# LautIO.net
KiCad netlist of a schematic drawn in EAGLE
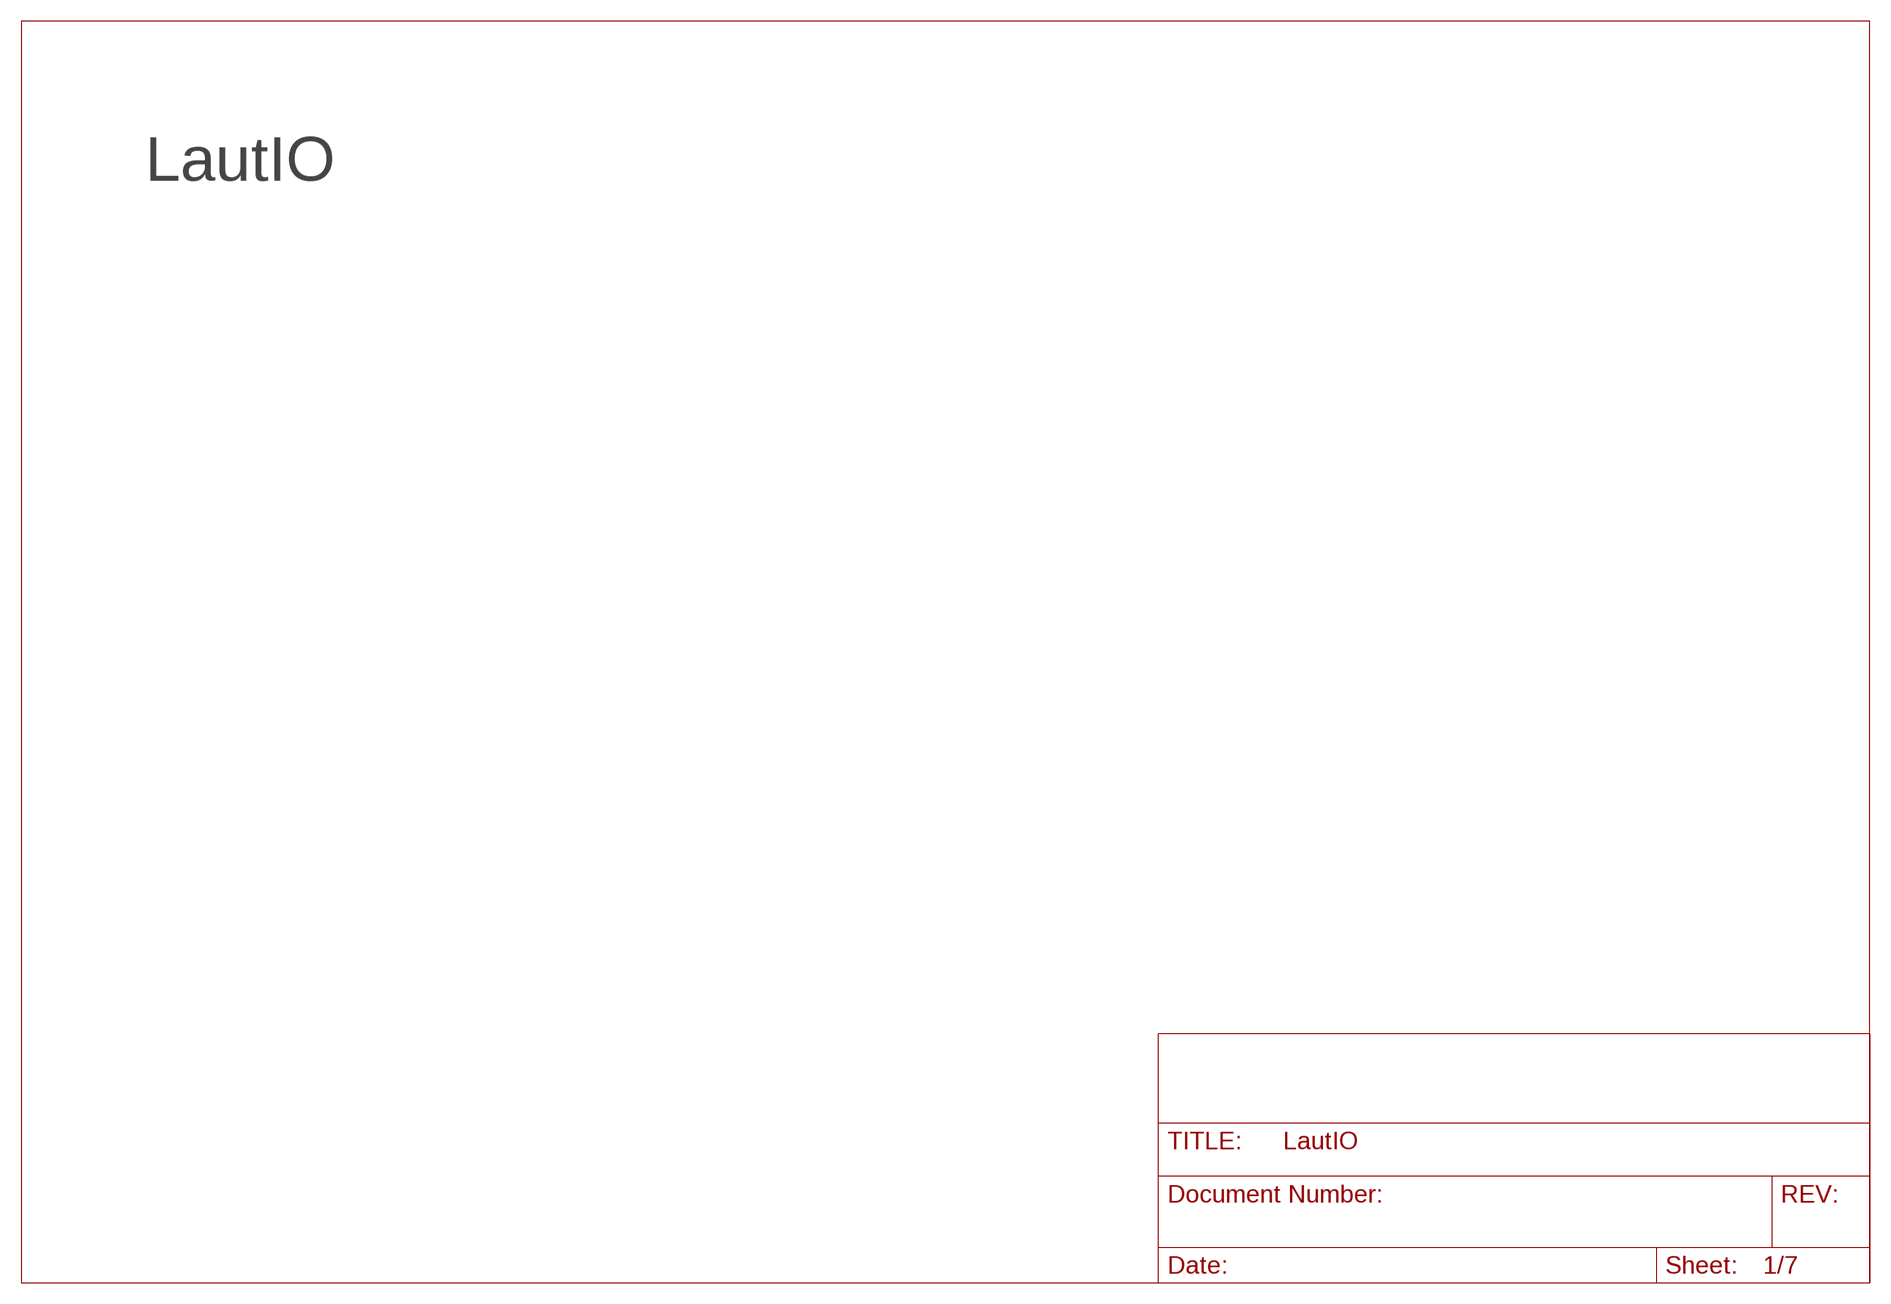
[diagram p0: schematic, sheet 1]
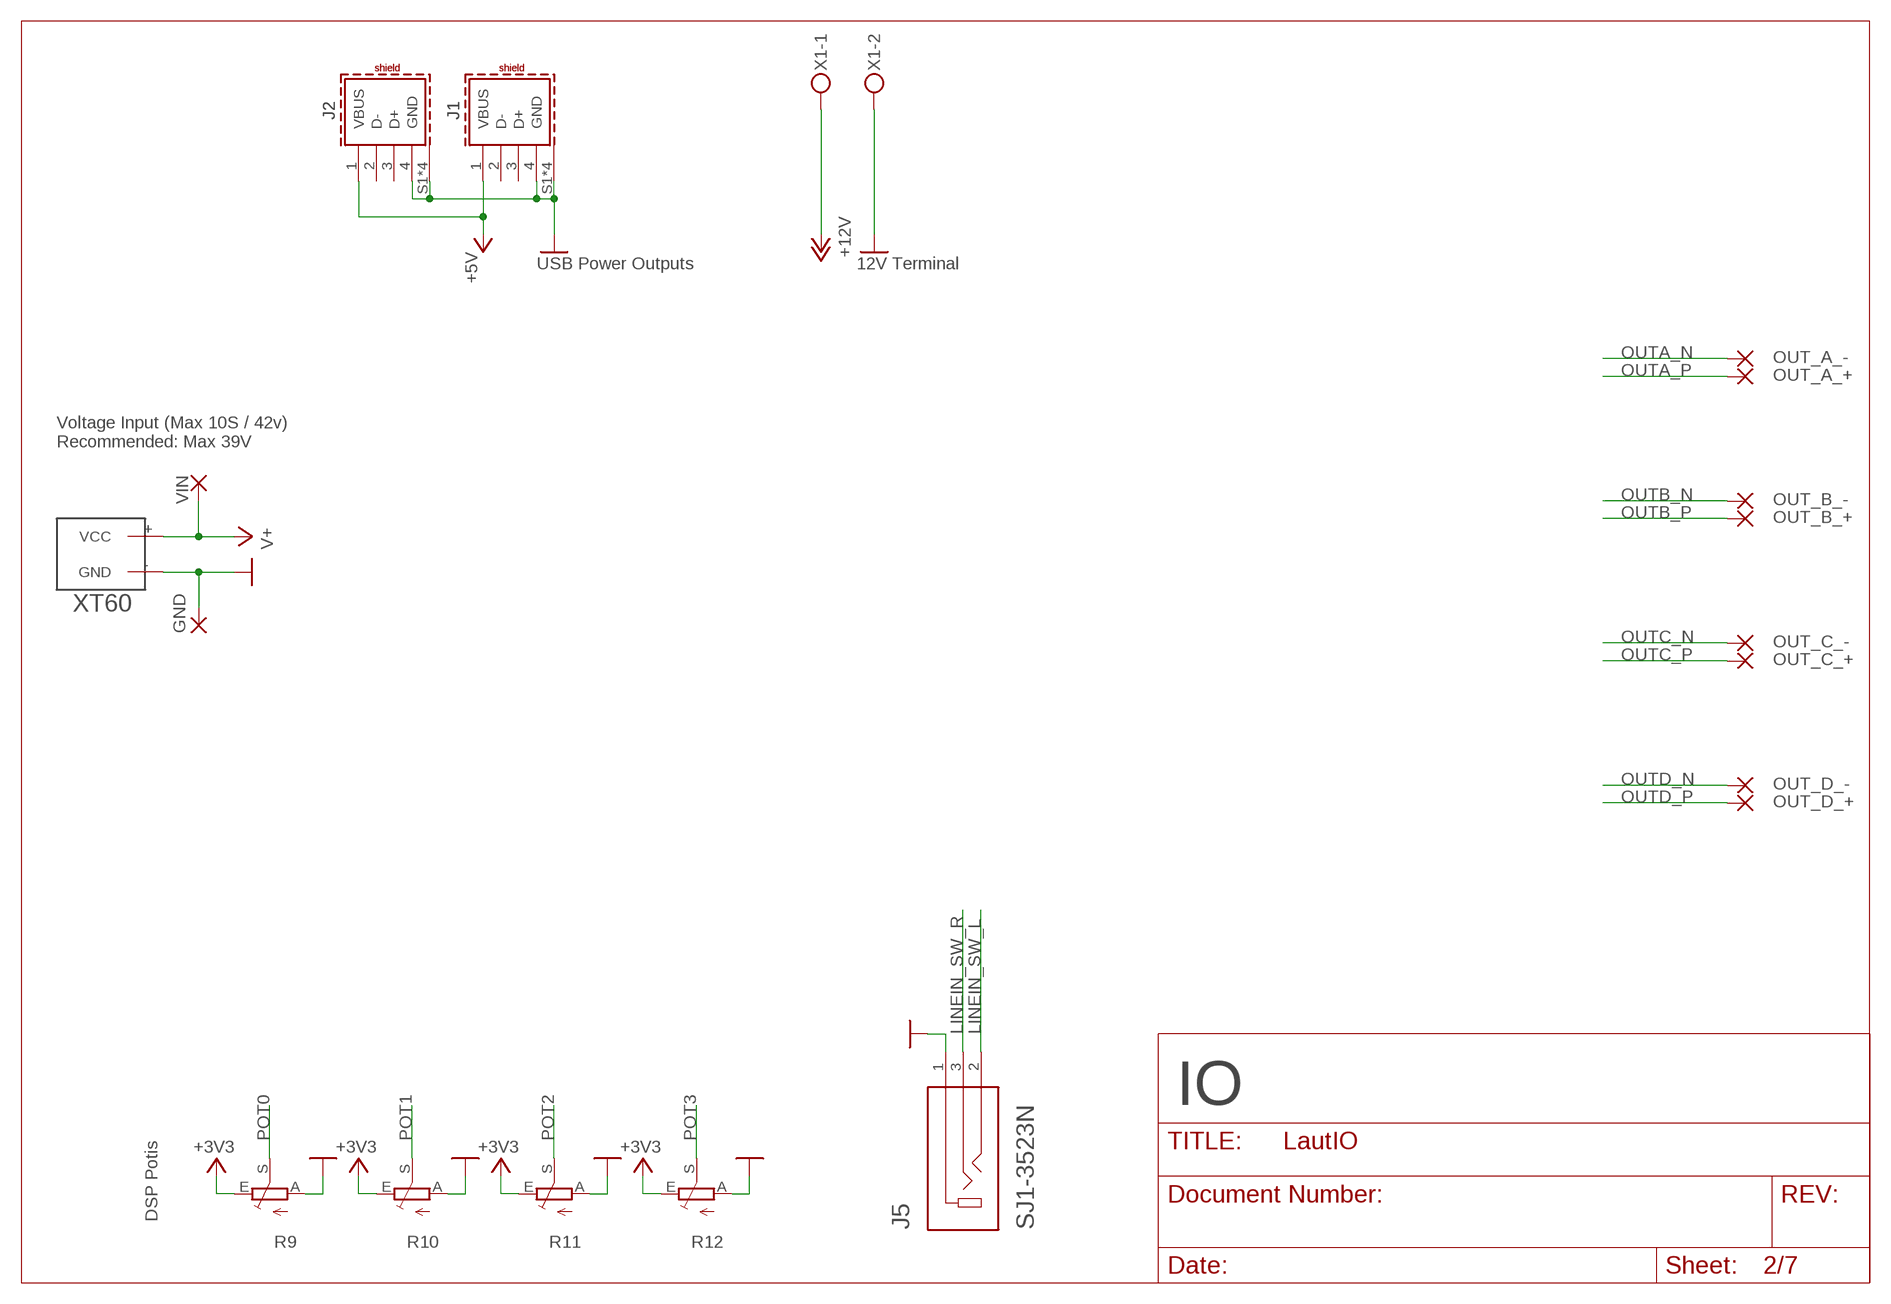
[diagram p1: schematic, sheet 2]
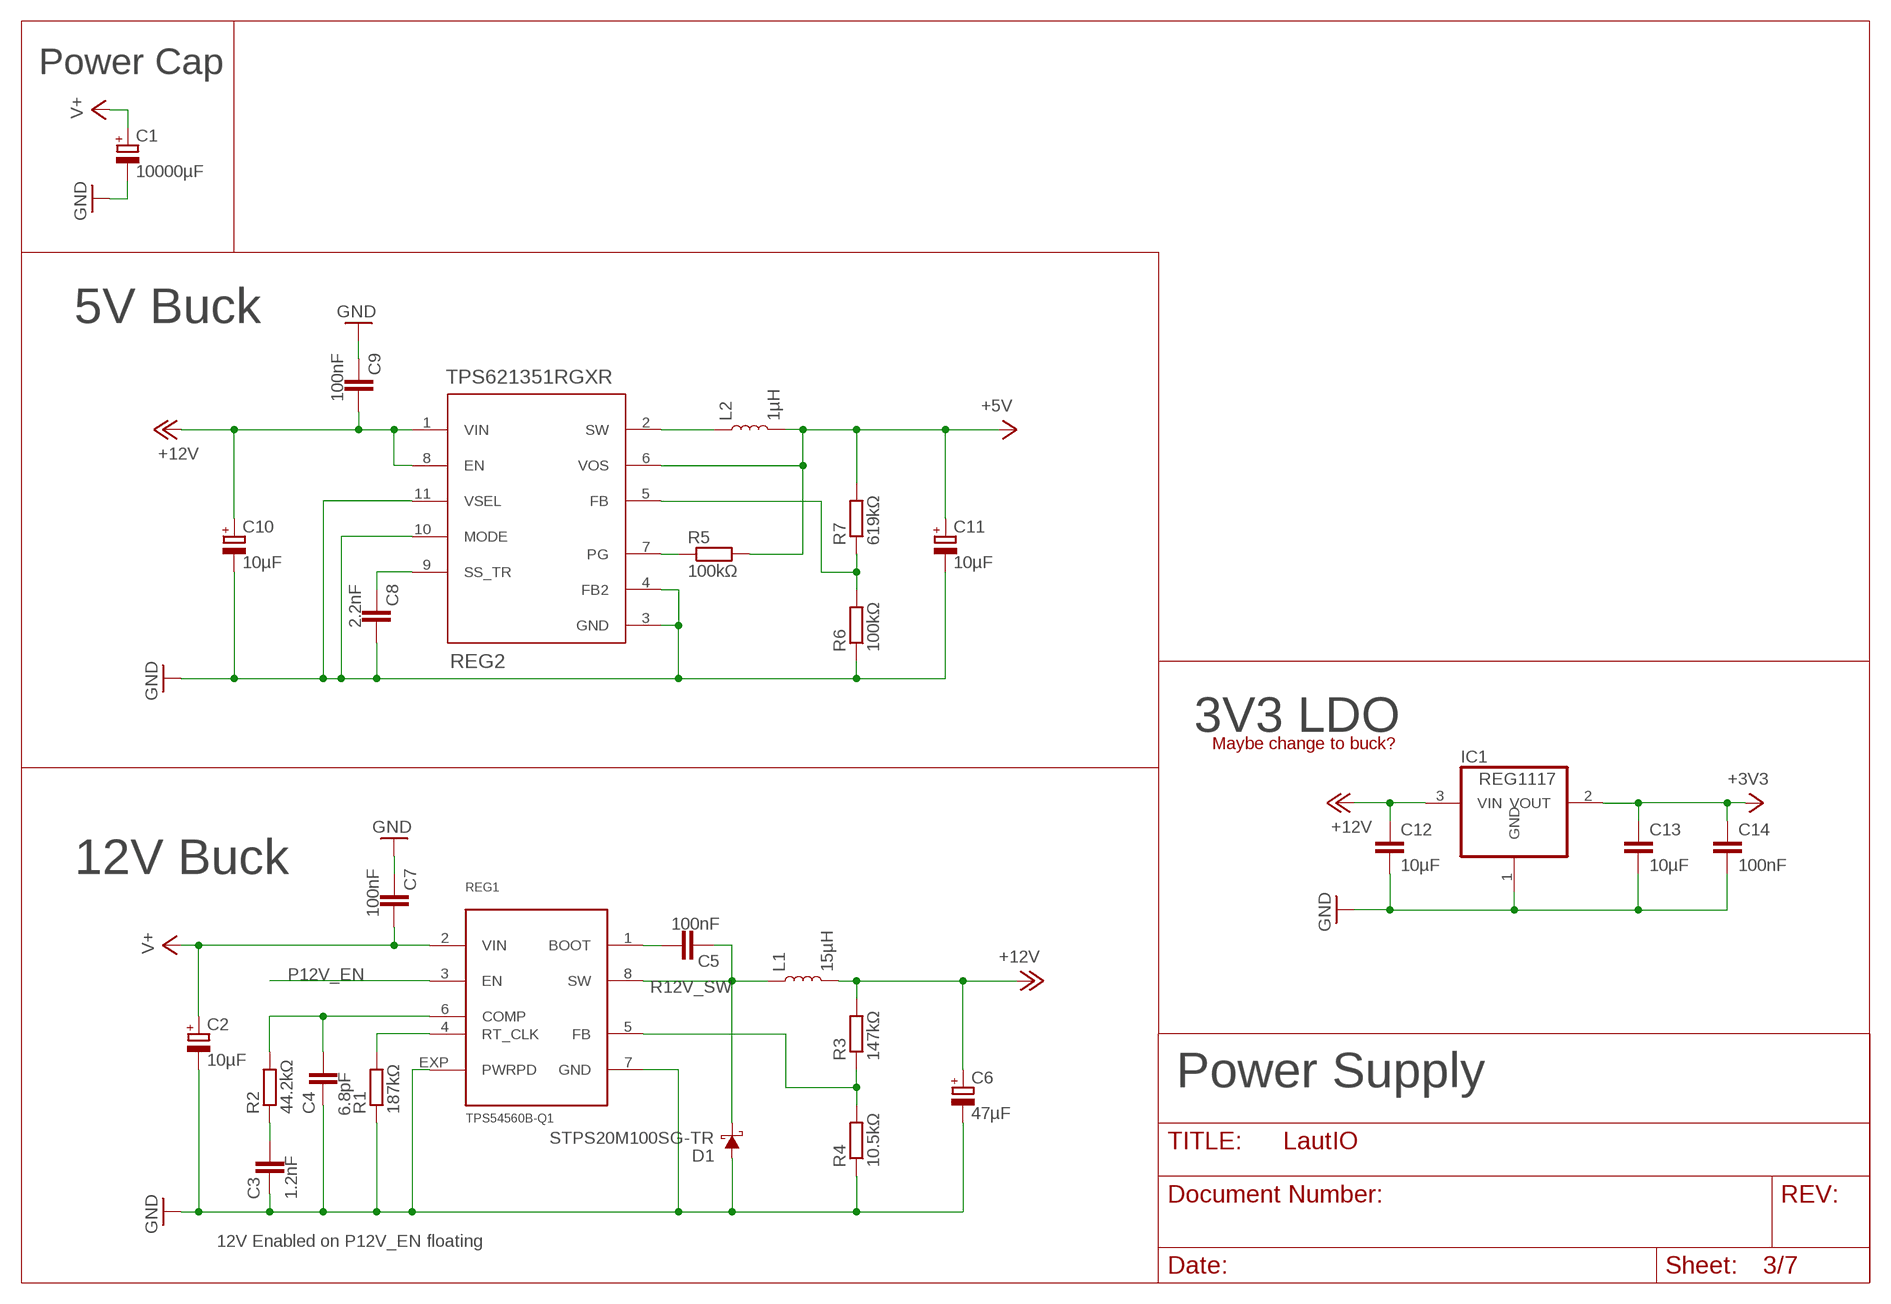
[diagram p2: schematic, sheet 3]
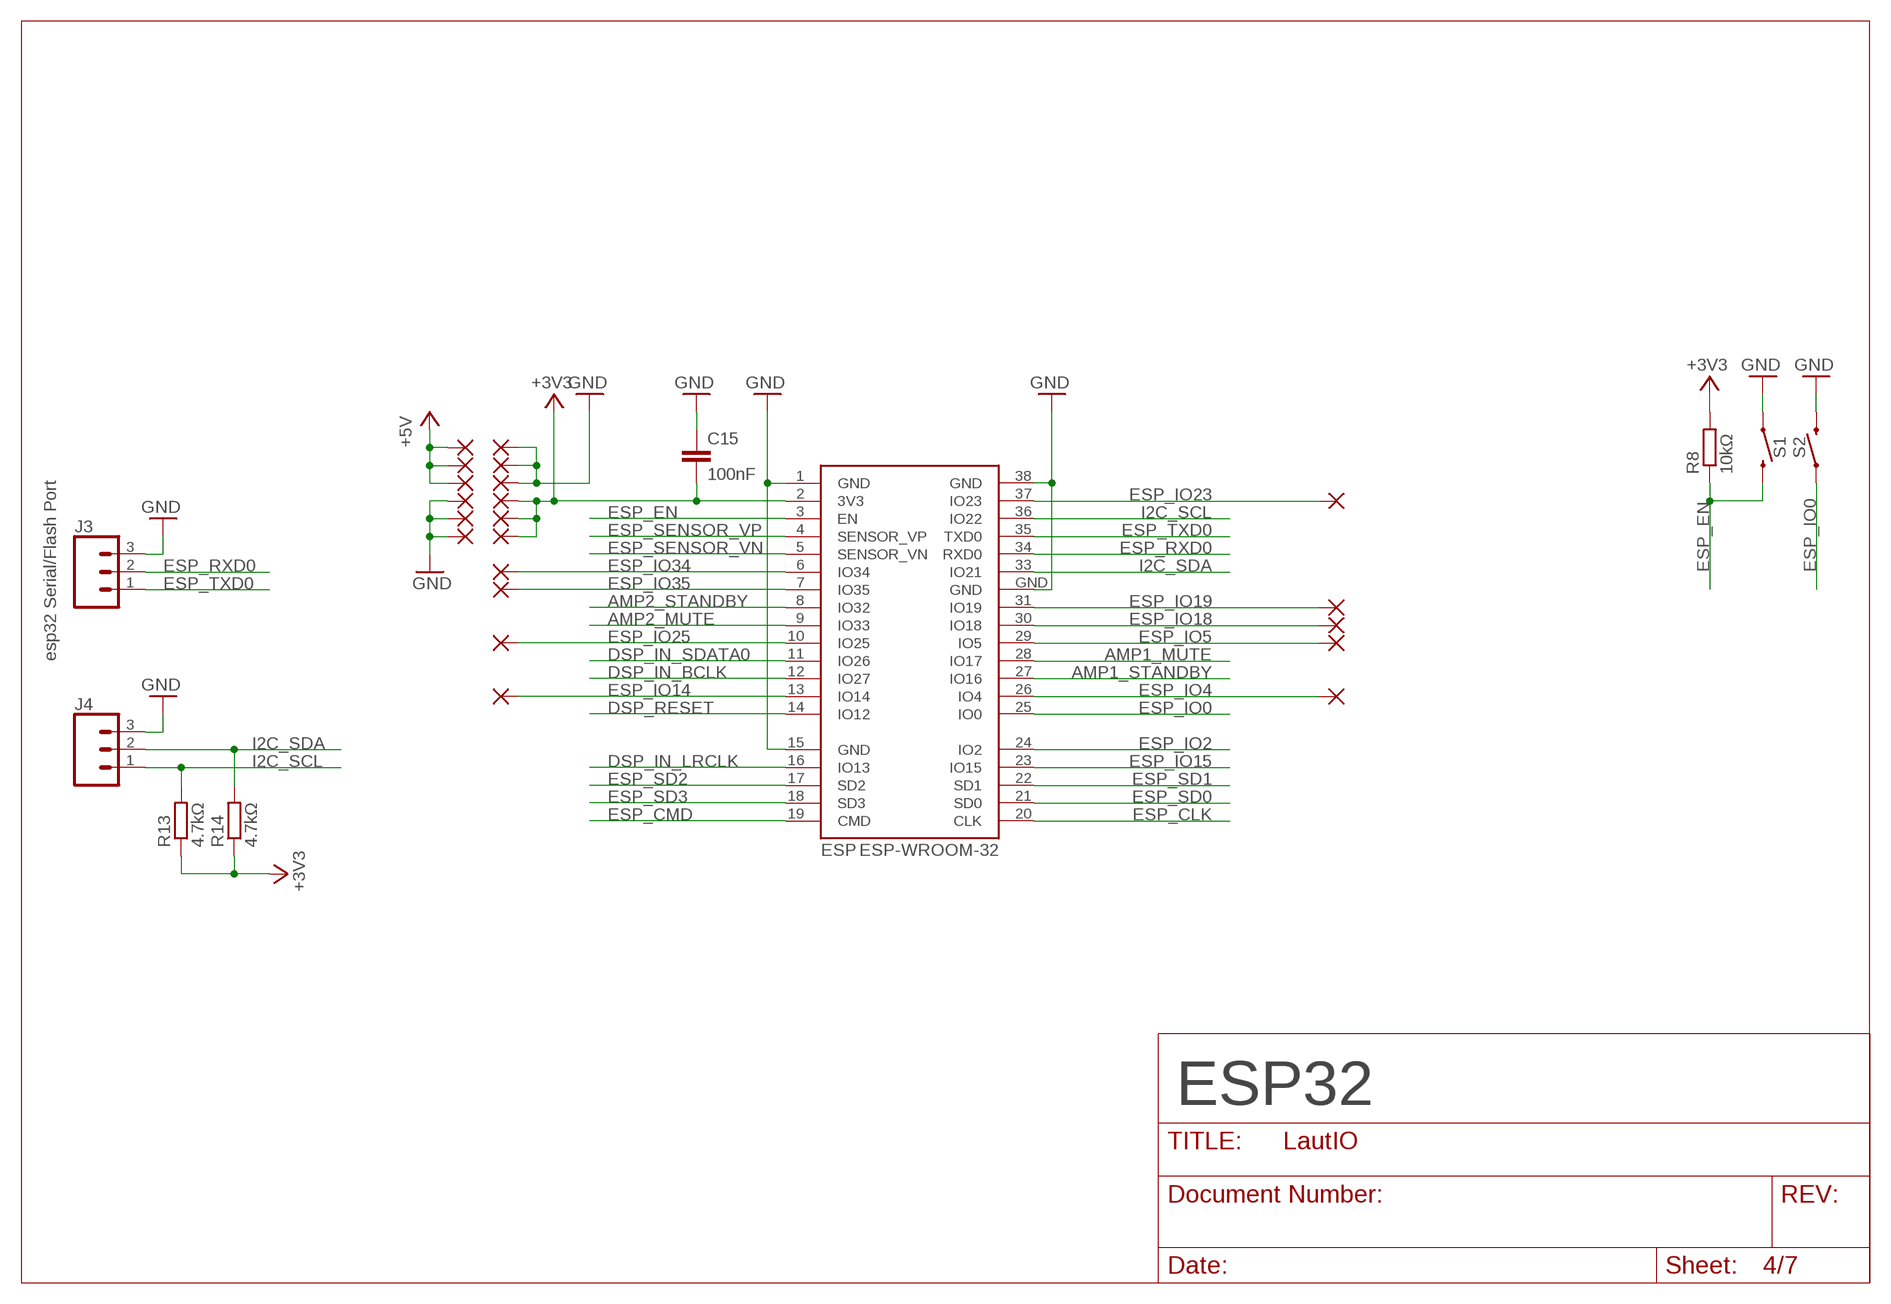
[diagram p3: schematic, sheet 4]
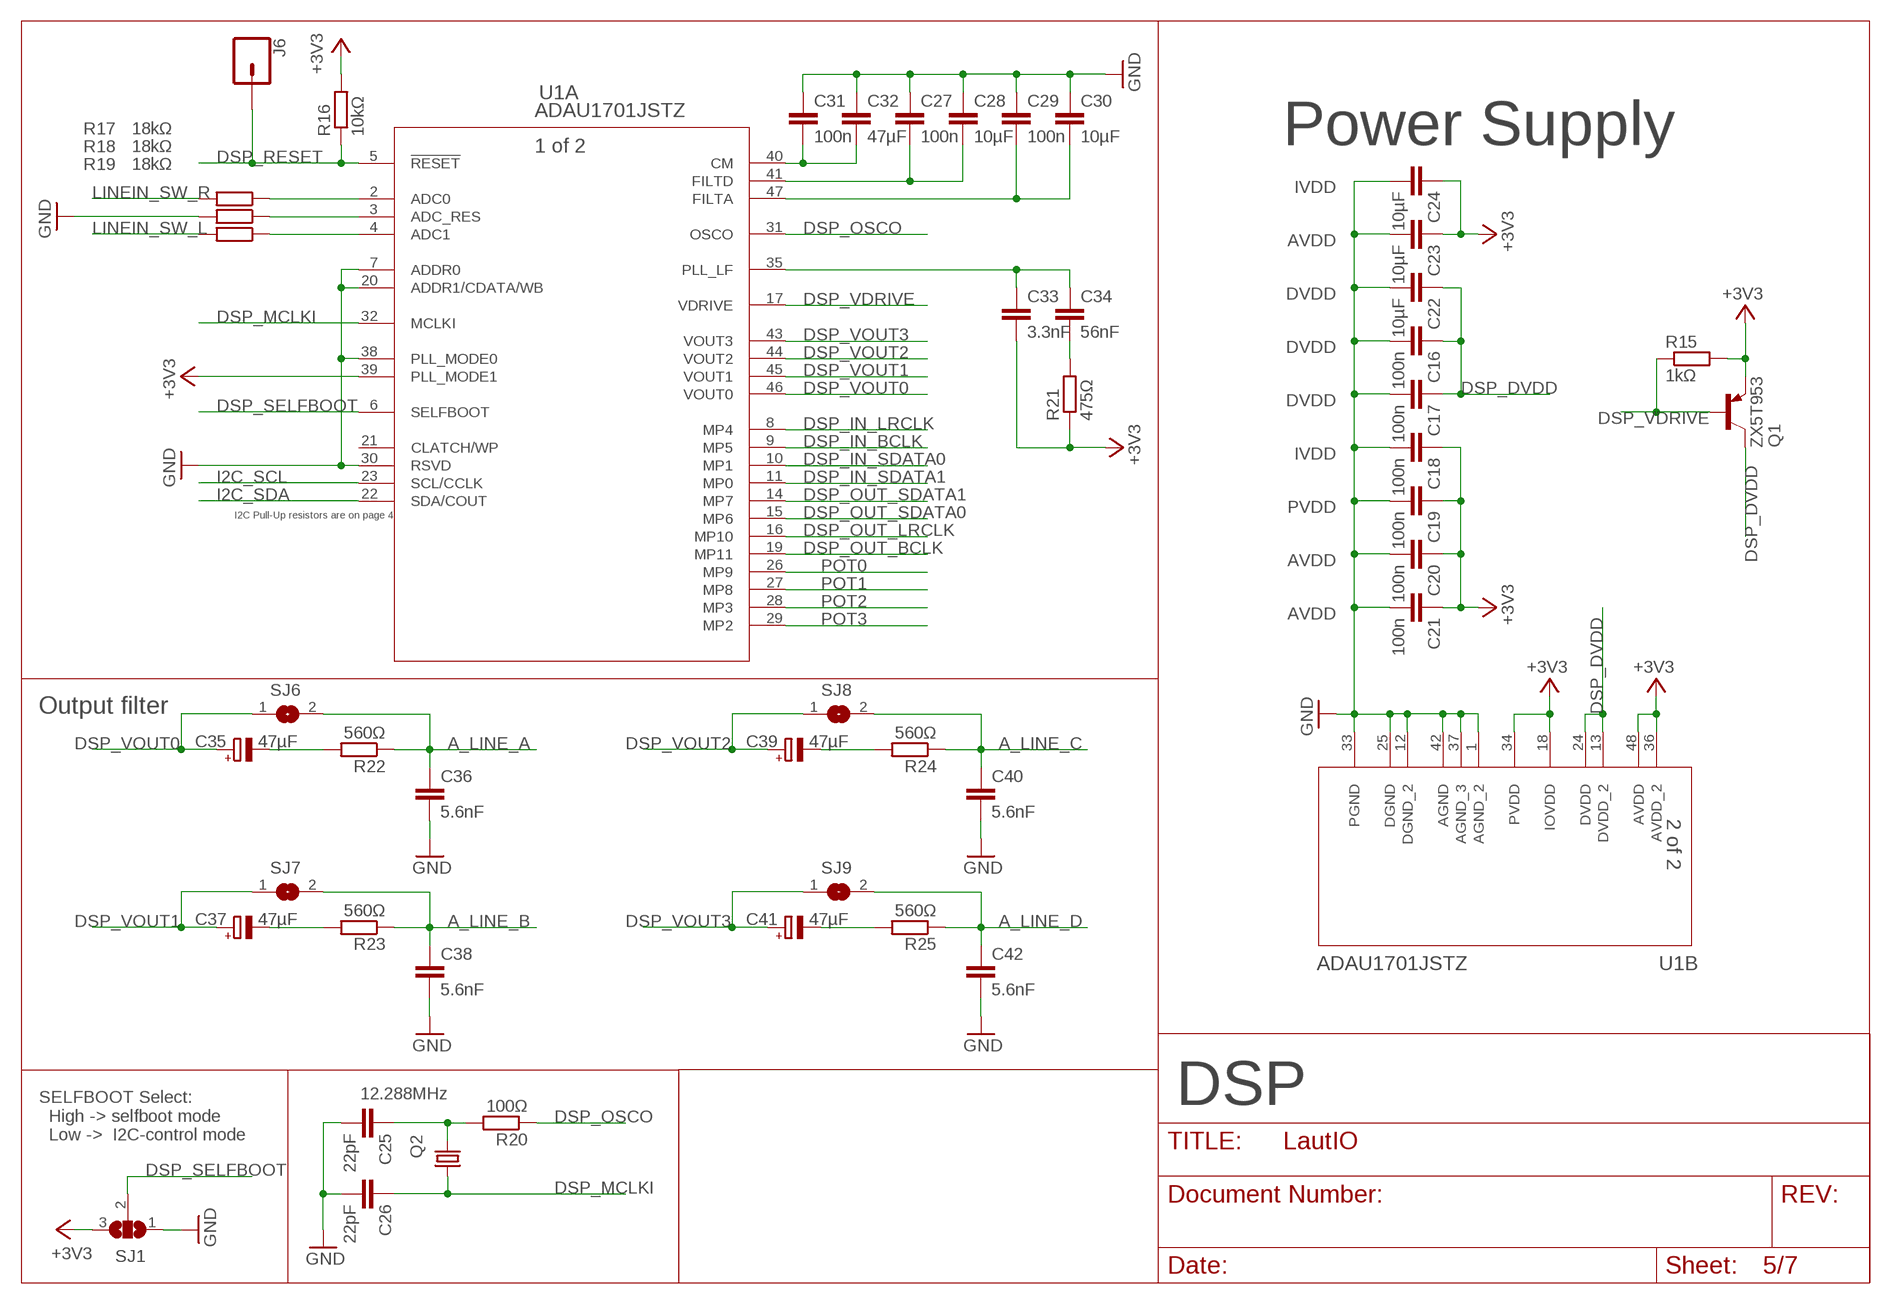
[diagram p4: schematic, sheet 5]
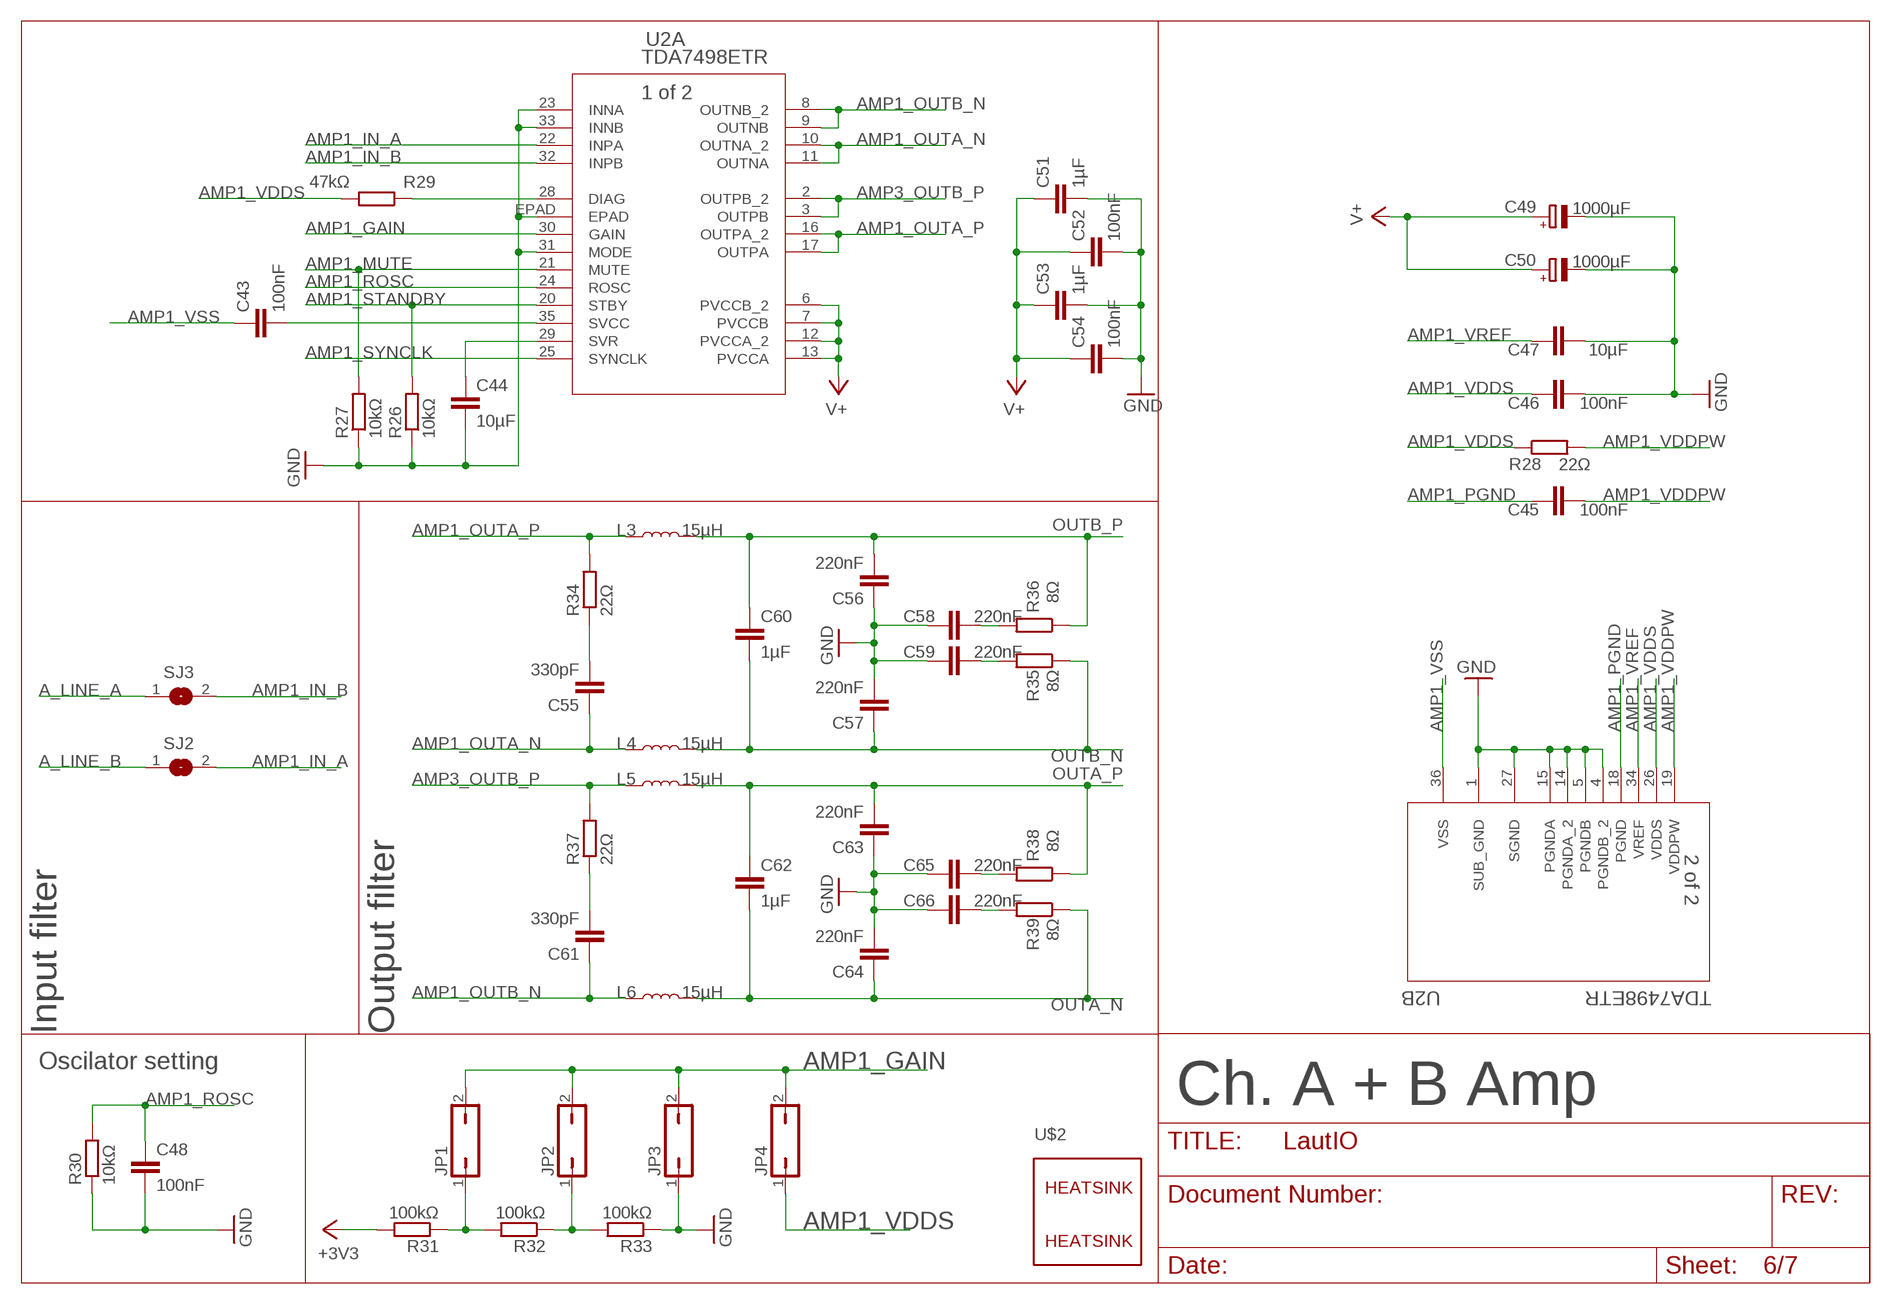
[diagram p5: schematic, sheet 6]
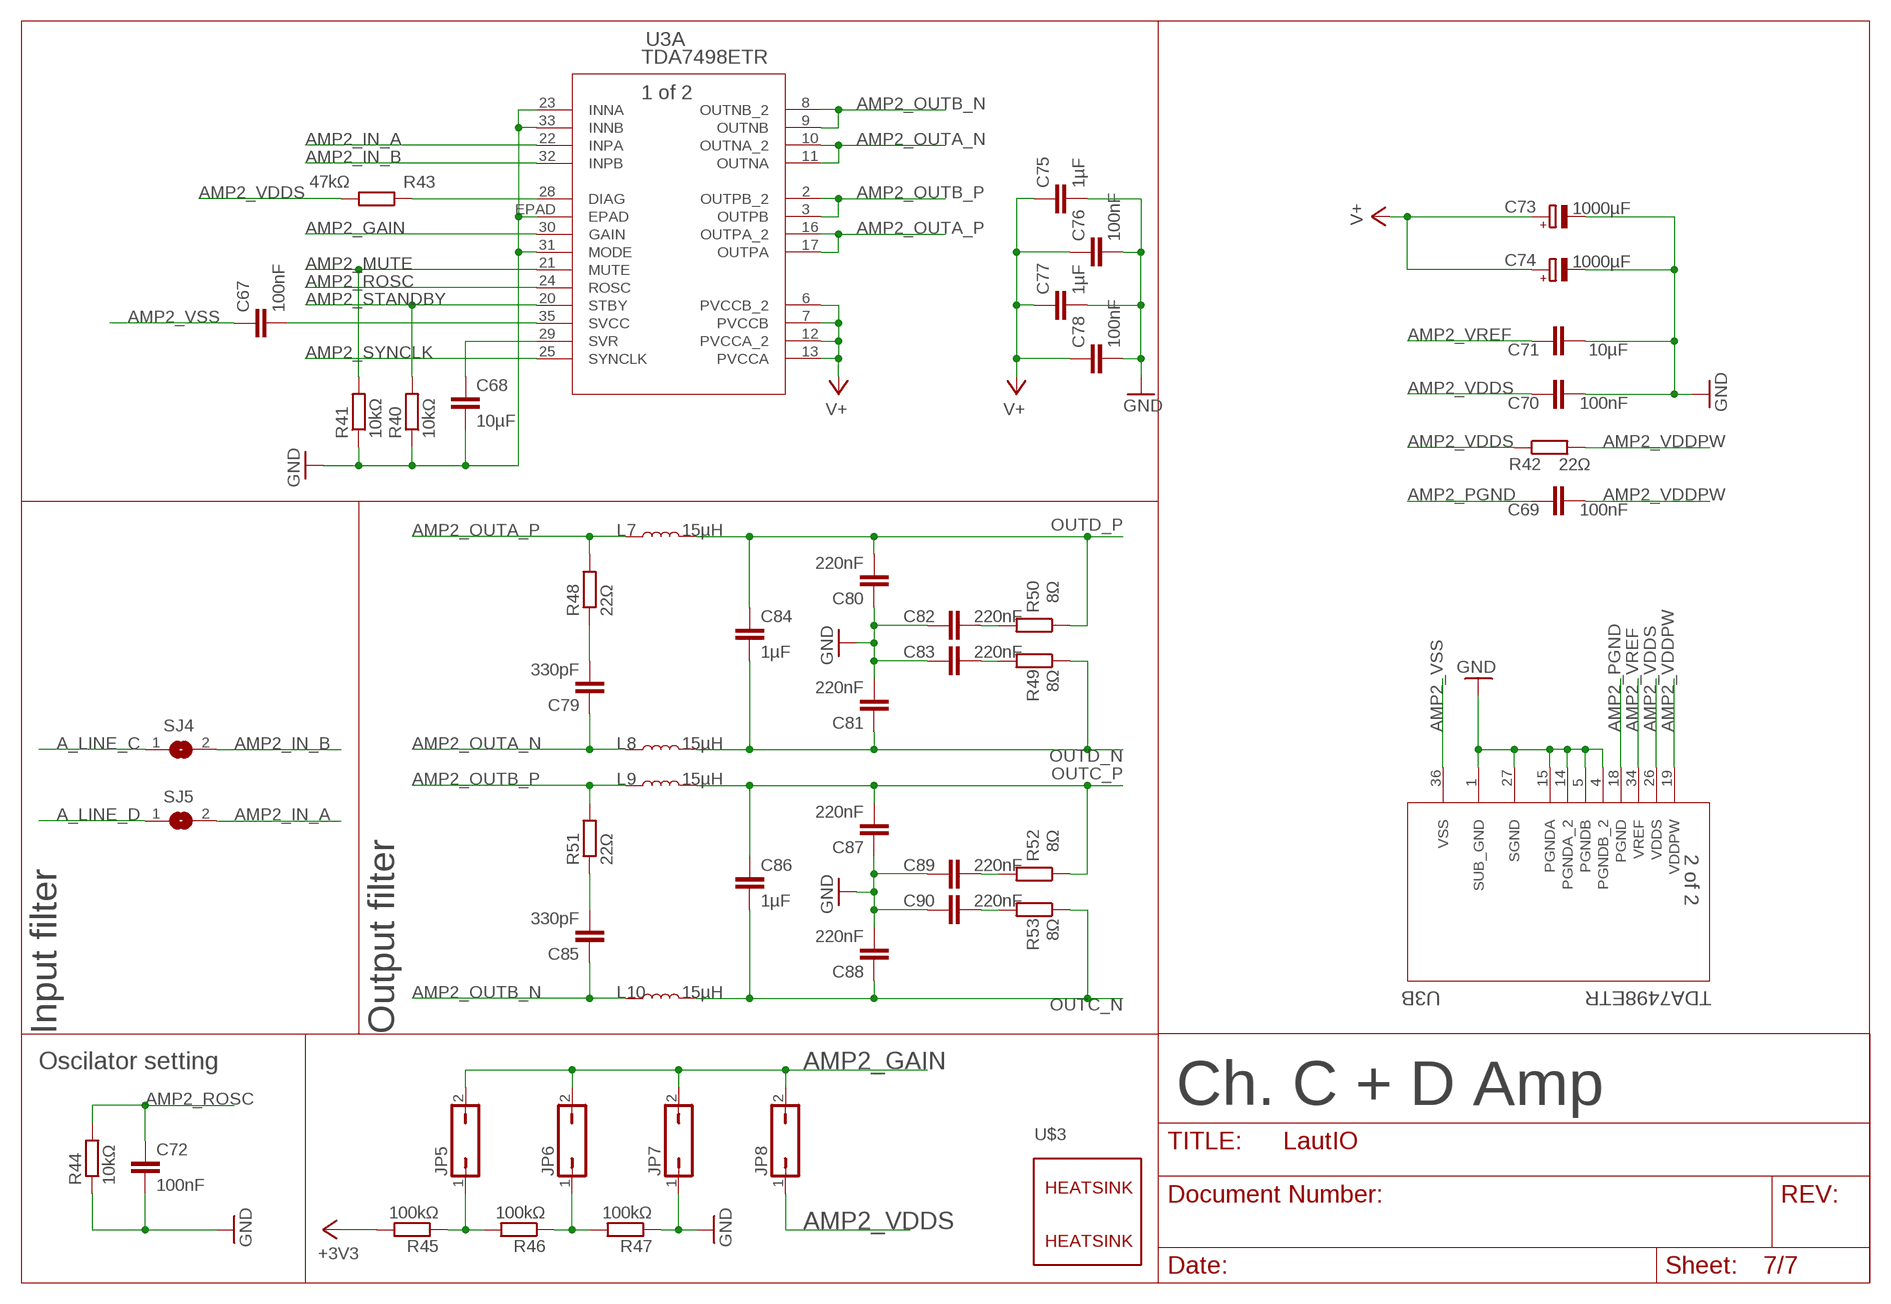
[diagram p6: schematic, sheet 7]

(export (version "E")
  (design (tool "Eeschema 10.0.6"))
  (components
    (comp (ref "C1")
      (value "10000µF")
      (footprint "eagle-import:EB35D")
      (libsource (lib "eagle-import") (part "CPOL-EUE10-35"))
    )
    (comp (ref "C2")
      (value "10µF")
      (footprint "eagle-import:153CLV-0605")
      (libsource (lib "eagle-import") (part "CPOL-EU153CLV-0605"))
    )
    (comp (ref "C3")
      (value "1.2nF")
      (footprint "eagle-import:C0603")
      (libsource (lib "eagle-import") (part "C-EUC0603"))
    )
    (comp (ref "C4")
      (value "6.8pF")
      (footprint "eagle-import:C0603")
      (libsource (lib "eagle-import") (part "C-EUC0603"))
    )
    (comp (ref "C5")
      (value "100nF")
      (footprint "eagle-import:C0603")
      (libsource (lib "eagle-import") (part "C-EUC0603"))
    )
    (comp (ref "C6")
      (value "47µF")
      (footprint "eagle-import:153CLV-0807")
      (libsource (lib "eagle-import") (part "CPOL-EU153CLV-0807"))
    )
    (comp (ref "C7")
      (value "100nF")
      (footprint "eagle-import:C0603")
      (libsource (lib "eagle-import") (part "C-EUC0603"))
    )
    (comp (ref "C8")
      (value "2.2nF")
      (footprint "eagle-import:C0603")
      (libsource (lib "eagle-import") (part "C-EUC0603"))
    )
    (comp (ref "C9")
      (value "100nF")
      (footprint "eagle-import:C0603")
      (libsource (lib "eagle-import") (part "C-EUC0603"))
    )
    (comp (ref "C10")
      (value "10µF")
      (footprint "eagle-import:153CLV-0605")
      (libsource (lib "eagle-import") (part "CPOL-EU153CLV-0605"))
    )
    (comp (ref "C11")
      (value "10µF")
      (footprint "eagle-import:153CLV-0605")
      (libsource (lib "eagle-import") (part "CPOL-EU153CLV-0605"))
    )
    (comp (ref "C12")
      (value "10µF")
      (footprint "eagle-import:C1206")
      (libsource (lib "eagle-import") (part "C-EUC1206"))
    )
    (comp (ref "C13")
      (value "10µF")
      (footprint "eagle-import:C1206")
      (libsource (lib "eagle-import") (part "C-EUC1206"))
    )
    (comp (ref "C14")
      (value "100nF")
      (footprint "eagle-import:C0603")
      (libsource (lib "eagle-import") (part "C-EUC0603"))
    )
    (comp (ref "D1")
      (value "STPS20M100SG-TR")
      (footprint "eagle-import:TO-263_D2PAK")
      (libsource (lib "eagle-import") (part "STPS20M100SG-TR"))
    )
    (comp (ref "IC1")
      (value "REG1117")
      (footprint "eagle-import:SOT223")
      (libsource (lib "eagle-import") (part "REG1117"))
    )
    (comp (ref "L1")
      (value "15µH")
      (footprint "eagle-import:INDUCTOR_SDR1307")
      (libsource (lib "eagle-import") (part "INDUCTOR-SDR13-27UH"))
    )
    (comp (ref "L2")
      (value "1µH")
      (footprint "eagle-import:INDUCTOR_4X4MM")
      (libsource (lib "eagle-import") (part "4.7μH_SHIELDED_INDUCTORNPIS_LS"))
    )
    (comp (ref "R1")
      (value "187kΩ")
      (footprint "eagle-import:R0603")
      (libsource (lib "eagle-import") (part "R-EU_R0603"))
    )
    (comp (ref "R2")
      (value "44.2kΩ")
      (footprint "eagle-import:R0603")
      (libsource (lib "eagle-import") (part "R-EU_R0603"))
    )
    (comp (ref "R3")
      (value "147kΩ")
      (footprint "eagle-import:R0603")
      (libsource (lib "eagle-import") (part "R-EU_R0603"))
    )
    (comp (ref "R4")
      (value "10.5kΩ")
      (footprint "eagle-import:R0603")
      (libsource (lib "eagle-import") (part "R-EU_R0603"))
    )
    (comp (ref "R5")
      (value "100kΩ")
      (footprint "eagle-import:R0603")
      (libsource (lib "eagle-import") (part "R-EU_R0603"))
    )
    (comp (ref "R6")
      (value "100kΩ")
      (footprint "eagle-import:R0603")
      (libsource (lib "eagle-import") (part "R-EU_R0603"))
    )
    (comp (ref "R7")
      (value "619kΩ")
      (footprint "eagle-import:R0603")
      (libsource (lib "eagle-import") (part "R-EU_R0603"))
    )
    (comp (ref "REG1")
      (value "TPS54560B-Q1")
      (footprint "eagle-import:HSOP8")
      (libsource (lib "eagle-import") (part "TPS54560B-Q1"))
    )
    (comp (ref "REG2")
      (value "TPS621351RGXR")
      (footprint "eagle-import:RGX0011A")
      (fields (field (name "MF") "Texas Instruments"))
      (libsource (lib "eagle-import") (part "TPS621351RGXR"))
    )
    (comp (ref "C16")
      (value "100n")
      (footprint "eagle-import:C0603")
      (libsource (lib "eagle-import") (part "C-EUC0603"))
    )
    (comp (ref "C17")
      (value "100n")
      (footprint "eagle-import:C0603")
      (libsource (lib "eagle-import") (part "C-EUC0603"))
    )
    (comp (ref "C18")
      (value "100n")
      (footprint "eagle-import:C0603")
      (libsource (lib "eagle-import") (part "C-EUC0603"))
    )
    (comp (ref "C19")
      (value "100n")
      (footprint "eagle-import:C0603")
      (libsource (lib "eagle-import") (part "C-EUC0603"))
    )
    (comp (ref "C20")
      (value "100n")
      (footprint "eagle-import:C0603")
      (libsource (lib "eagle-import") (part "C-EUC0603"))
    )
    (comp (ref "C21")
      (value "100n")
      (footprint "eagle-import:C0603")
      (libsource (lib "eagle-import") (part "C-EUC0603"))
    )
    (comp (ref "C22")
      (value "10µF")
      (footprint "eagle-import:C1206K")
      (libsource (lib "eagle-import") (part "C-EUC1206K"))
    )
    (comp (ref "C23")
      (value "10µF")
      (footprint "eagle-import:C1206K")
      (libsource (lib "eagle-import") (part "C-EUC1206K"))
    )
    (comp (ref "C24")
      (value "10µF")
      (footprint "eagle-import:C1206K")
      (libsource (lib "eagle-import") (part "C-EUC1206K"))
    )
    (comp (ref "C25")
      (value "22pF")
      (footprint "eagle-import:C0603")
      (libsource (lib "eagle-import") (part "C-EUC0603"))
    )
    (comp (ref "C26")
      (value "22pF")
      (footprint "eagle-import:C0603")
      (libsource (lib "eagle-import") (part "C-EUC0603"))
    )
    (comp (ref "C27")
      (value "100n")
      (footprint "eagle-import:C0603")
      (libsource (lib "eagle-import") (part "C-EUC0603"))
    )
    (comp (ref "C28")
      (value "10µF")
      (footprint "eagle-import:C1206K")
      (libsource (lib "eagle-import") (part "C-EUC1206K"))
    )
    (comp (ref "C29")
      (value "100n")
      (footprint "eagle-import:C0603")
      (libsource (lib "eagle-import") (part "C-EUC0603"))
    )
    (comp (ref "C30")
      (value "10µF")
      (footprint "eagle-import:C1206K")
      (libsource (lib "eagle-import") (part "C-EUC1206K"))
    )
    (comp (ref "C31")
      (value "100n")
      (footprint "eagle-import:C0603")
      (libsource (lib "eagle-import") (part "C-EUC0603"))
    )
    (comp (ref "C32")
      (value "47µF")
      (footprint "eagle-import:C1206K")
      (libsource (lib "eagle-import") (part "C-EUC1206K"))
    )
    (comp (ref "C33")
      (value "3.3nF")
      (footprint "eagle-import:C0603")
      (libsource (lib "eagle-import") (part "C-EUC0603"))
    )
    (comp (ref "C34")
      (value "56nF")
      (footprint "eagle-import:C0603")
      (libsource (lib "eagle-import") (part "C-EUC0603"))
    )
    (comp (ref "C35")
      (value "47µF")
      (footprint "eagle-import:153CLV-0605")
      (libsource (lib "eagle-import") (part "CPOL-EU153CLV-0605"))
    )
    (comp (ref "C36")
      (value "5.6nF")
      (footprint "eagle-import:C0603")
      (libsource (lib "eagle-import") (part "C-EUC0603"))
    )
    (comp (ref "C37")
      (value "47µF")
      (footprint "eagle-import:153CLV-0605")
      (libsource (lib "eagle-import") (part "CPOL-EU153CLV-0605"))
    )
    (comp (ref "C38")
      (value "5.6nF")
      (footprint "eagle-import:C0603")
      (libsource (lib "eagle-import") (part "C-EUC0603"))
    )
    (comp (ref "C39")
      (value "47µF")
      (footprint "eagle-import:153CLV-0605")
      (libsource (lib "eagle-import") (part "CPOL-EU153CLV-0605"))
    )
    (comp (ref "C40")
      (value "5.6nF")
      (footprint "eagle-import:C0603")
      (libsource (lib "eagle-import") (part "C-EUC0603"))
    )
    (comp (ref "C41")
      (value "47µF")
      (footprint "eagle-import:153CLV-0605")
      (libsource (lib "eagle-import") (part "CPOL-EU153CLV-0605"))
    )
    (comp (ref "C42")
      (value "5.6nF")
      (footprint "eagle-import:C0603")
      (libsource (lib "eagle-import") (part "C-EUC0603"))
    )
    (comp (ref "J6")
      (value "CONN_01")
      (footprint "eagle-import:1X01")
      (libsource (lib "eagle-import") (part "CONN_01"))
    )
    (comp (ref "Q1")
      (value "ZX5T953")
      (footprint "eagle-import:SOT223")
      (libsource (lib "eagle-import") (part "FZT753SMD"))
    )
    (comp (ref "Q2")
      (value "12.288MHz")
      (footprint "eagle-import:CSM-7X-DU")
      (libsource (lib "eagle-import") (part "CSM-7X-DU"))
    )
    (comp (ref "R15")
      (value "1kΩ")
      (footprint "eagle-import:R0603")
      (libsource (lib "eagle-import") (part "R-EU_R0603"))
    )
    (comp (ref "R16")
      (value "10kΩ")
      (footprint "eagle-import:R0603")
      (libsource (lib "eagle-import") (part "R-EU_R0603"))
    )
    (comp (ref "R17")
      (value "18kΩ")
      (footprint "eagle-import:R0603")
      (libsource (lib "eagle-import") (part "R-EU_R0603"))
    )
    (comp (ref "R18")
      (value "18kΩ")
      (footprint "eagle-import:R0603")
      (libsource (lib "eagle-import") (part "R-EU_R0603"))
    )
    (comp (ref "R19")
      (value "18kΩ")
      (footprint "eagle-import:R0603")
      (libsource (lib "eagle-import") (part "R-EU_R0603"))
    )
    (comp (ref "R20")
      (value "100Ω")
      (footprint "eagle-import:R0603")
      (libsource (lib "eagle-import") (part "R-EU_R0603"))
    )
    (comp (ref "R21")
      (value "475Ω")
      (footprint "eagle-import:R0603")
      (libsource (lib "eagle-import") (part "R-EU_R0603"))
    )
    (comp (ref "R22")
      (value "560Ω")
      (footprint "eagle-import:R0603")
      (libsource (lib "eagle-import") (part "R-EU_R0603"))
    )
    (comp (ref "R23")
      (value "560Ω")
      (footprint "eagle-import:R0603")
      (libsource (lib "eagle-import") (part "R-EU_R0603"))
    )
    (comp (ref "R24")
      (value "560Ω")
      (footprint "eagle-import:R0603")
      (libsource (lib "eagle-import") (part "R-EU_R0603"))
    )
    (comp (ref "R25")
      (value "560Ω")
      (footprint "eagle-import:R0603")
      (libsource (lib "eagle-import") (part "R-EU_R0603"))
    )
    (comp (ref "SJ1")
      (value "SJ2W")
      (footprint "eagle-import:SJ_2")
      (libsource (lib "eagle-import") (part "SJ2W"))
    )
    (comp (ref "SJ6") (value "SJ") (footprint "eagle-import:SJ") (libsource (lib "eagle-import") (part "SJ")))
    (comp (ref "SJ7") (value "SJ") (footprint "eagle-import:SJ") (libsource (lib "eagle-import") (part "SJ")))
    (comp (ref "SJ8") (value "SJ") (footprint "eagle-import:SJ") (libsource (lib "eagle-import") (part "SJ")))
    (comp (ref "SJ9") (value "SJ") (footprint "eagle-import:SJ") (libsource (lib "eagle-import") (part "SJ")))
    (comp (ref "U1")
      (value "ADAU1701JSTZ")
      (footprint "eagle-import:ST_48_ADI")
      (libsource (lib "eagle-import") (part "ADAU1701JSTZ"))
    )
    (comp (ref "C43")
      (value "100nF")
      (footprint "eagle-import:C0603")
      (libsource (lib "eagle-import") (part "C-EUC0603"))
    )
    (comp (ref "C44")
      (value "10µF")
      (footprint "eagle-import:C1206K")
      (libsource (lib "eagle-import") (part "C-EUC1206K"))
    )
    (comp (ref "C45")
      (value "100nF")
      (footprint "eagle-import:C0603")
      (libsource (lib "eagle-import") (part "C-EUC0603"))
    )
    (comp (ref "C46")
      (value "100nF")
      (footprint "eagle-import:C0603")
      (libsource (lib "eagle-import") (part "C-EUC0603"))
    )
    (comp (ref "C47")
      (value "10µF")
      (footprint "eagle-import:C1206K")
      (libsource (lib "eagle-import") (part "C-EUC1206K"))
    )
    (comp (ref "C48")
      (value "100nF")
      (footprint "eagle-import:C0603")
      (libsource (lib "eagle-import") (part "C-EUC0603"))
    )
    (comp (ref "C49")
      (value "1000µF")
      (footprint "eagle-import:E7,5-16")
      (libsource (lib "eagle-import") (part "CPOL-EUE7.5-16"))
    )
    (comp (ref "C50")
      (value "1000µF")
      (footprint "eagle-import:E7,5-16")
      (libsource (lib "eagle-import") (part "CPOL-EUE7.5-16"))
    )
    (comp (ref "C51")
      (value "1µF")
      (footprint "eagle-import:C0603")
      (libsource (lib "eagle-import") (part "C-EUC0603"))
    )
    (comp (ref "C52")
      (value "100nF")
      (footprint "eagle-import:C0603")
      (libsource (lib "eagle-import") (part "C-EUC0603"))
    )
    (comp (ref "C53")
      (value "1µF")
      (footprint "eagle-import:C0603")
      (libsource (lib "eagle-import") (part "C-EUC0603"))
    )
    (comp (ref "C54")
      (value "100nF")
      (footprint "eagle-import:C0603")
      (libsource (lib "eagle-import") (part "C-EUC0603"))
    )
    (comp (ref "C55")
      (value "330pF")
      (footprint "eagle-import:C0603")
      (libsource (lib "eagle-import") (part "C-EUC0603"))
    )
    (comp (ref "C56")
      (value "220nF")
      (footprint "eagle-import:C0603")
      (libsource (lib "eagle-import") (part "C-EUC0603"))
    )
    (comp (ref "C57")
      (value "220nF")
      (footprint "eagle-import:C0603")
      (libsource (lib "eagle-import") (part "C-EUC0603"))
    )
    (comp (ref "C58")
      (value "220nF")
      (footprint "eagle-import:C0603")
      (libsource (lib "eagle-import") (part "C-EUC0603"))
    )
    (comp (ref "C59")
      (value "220nF")
      (footprint "eagle-import:C0603")
      (libsource (lib "eagle-import") (part "C-EUC0603"))
    )
    (comp (ref "C60")
      (value "1µF")
      (footprint "eagle-import:C3640")
      (libsource (lib "eagle-import") (part "C-EUC3640"))
    )
    (comp (ref "C61")
      (value "330pF")
      (footprint "eagle-import:C0603")
      (libsource (lib "eagle-import") (part "C-EUC0603"))
    )
    (comp (ref "C62")
      (value "1µF")
      (footprint "eagle-import:C3640")
      (libsource (lib "eagle-import") (part "C-EUC3640"))
    )
    (comp (ref "C63")
      (value "220nF")
      (footprint "eagle-import:C0603")
      (libsource (lib "eagle-import") (part "C-EUC0603"))
    )
    (comp (ref "C64")
      (value "220nF")
      (footprint "eagle-import:C0603")
      (libsource (lib "eagle-import") (part "C-EUC0603"))
    )
    (comp (ref "C65")
      (value "220nF")
      (footprint "eagle-import:C0603")
      (libsource (lib "eagle-import") (part "C-EUC0603"))
    )
    (comp (ref "C66")
      (value "220nF")
      (footprint "eagle-import:C0603")
      (libsource (lib "eagle-import") (part "C-EUC0603"))
    )
    (comp (ref "JP1")
      (value "JP1Q")
      (footprint "eagle-import:JP1")
      (libsource (lib "eagle-import") (part "JP1Q"))
    )
    (comp (ref "JP2")
      (value "JP1Q")
      (footprint "eagle-import:JP1")
      (libsource (lib "eagle-import") (part "JP1Q"))
    )
    (comp (ref "JP3")
      (value "JP1Q")
      (footprint "eagle-import:JP1")
      (libsource (lib "eagle-import") (part "JP1Q"))
    )
    (comp (ref "JP4")
      (value "JP1Q")
      (footprint "eagle-import:JP1")
      (libsource (lib "eagle-import") (part "JP1Q"))
    )
    (comp (ref "L3")
      (value "15µH")
      (footprint "eagle-import:INDUCTOR_SDR1307")
      (libsource (lib "eagle-import") (part "INDUCTOR-SDR13-27UH"))
    )
    (comp (ref "L4")
      (value "15µH")
      (footprint "eagle-import:INDUCTOR_SDR1307")
      (libsource (lib "eagle-import") (part "INDUCTOR-SDR13-27UH"))
    )
    (comp (ref "L5")
      (value "15µH")
      (footprint "eagle-import:INDUCTOR_SDR1307")
      (libsource (lib "eagle-import") (part "INDUCTOR-SDR13-27UH"))
    )
    (comp (ref "L6")
      (value "15µH")
      (footprint "eagle-import:INDUCTOR_SDR1307")
      (libsource (lib "eagle-import") (part "INDUCTOR-SDR13-27UH"))
    )
    (comp (ref "R26")
      (value "10kΩ")
      (footprint "eagle-import:R0603")
      (libsource (lib "eagle-import") (part "R-EU_R0603"))
    )
    (comp (ref "R27")
      (value "10kΩ")
      (footprint "eagle-import:R0603")
      (libsource (lib "eagle-import") (part "R-EU_R0603"))
    )
    (comp (ref "R28")
      (value "22Ω")
      (footprint "eagle-import:R0603")
      (libsource (lib "eagle-import") (part "R-EU_R0603"))
    )
    (comp (ref "R29")
      (value "47kΩ")
      (footprint "eagle-import:R0603")
      (libsource (lib "eagle-import") (part "R-EU_R0603"))
    )
    (comp (ref "R30")
      (value "10kΩ")
      (footprint "eagle-import:R0603")
      (libsource (lib "eagle-import") (part "R-EU_R0603"))
    )
    (comp (ref "R31")
      (value "100kΩ")
      (footprint "eagle-import:R0603")
      (libsource (lib "eagle-import") (part "R-EU_R0603"))
    )
    (comp (ref "R32")
      (value "100kΩ")
      (footprint "eagle-import:R0603")
      (libsource (lib "eagle-import") (part "R-EU_R0603"))
    )
    (comp (ref "R33")
      (value "100kΩ")
      (footprint "eagle-import:R0603")
      (libsource (lib "eagle-import") (part "R-EU_R0603"))
    )
    (comp (ref "R34")
      (value "22Ω")
      (footprint "eagle-import:R0603")
      (libsource (lib "eagle-import") (part "R-EU_R0603"))
    )
    (comp (ref "R35")
      (value "8Ω")
      (footprint "eagle-import:R0603")
      (libsource (lib "eagle-import") (part "R-EU_R0603"))
    )
    (comp (ref "R36")
      (value "8Ω")
      (footprint "eagle-import:R0603")
      (libsource (lib "eagle-import") (part "R-EU_R0603"))
    )
    (comp (ref "R37")
      (value "22Ω")
      (footprint "eagle-import:R0603")
      (libsource (lib "eagle-import") (part "R-EU_R0603"))
    )
    (comp (ref "R38")
      (value "8Ω")
      (footprint "eagle-import:R0603")
      (libsource (lib "eagle-import") (part "R-EU_R0603"))
    )
    (comp (ref "R39")
      (value "8Ω")
      (footprint "eagle-import:R0603")
      (libsource (lib "eagle-import") (part "R-EU_R0603"))
    )
    (comp (ref "SJ2") (value "SJ") (footprint "eagle-import:SJ") (libsource (lib "eagle-import") (part "SJ")))
    (comp (ref "SJ3") (value "SJ") (footprint "eagle-import:SJ") (libsource (lib "eagle-import") (part "SJ")))
    (comp (ref "U$2")
      (value "ATS-CPX030030030")
      (footprint "eagle-import:ATS-CPX030030030")
      (libsource (lib "eagle-import") (part "ATS-CPX030030030"))
    )
    (comp (ref "U2")
      (value "TDA7498ETR")
      (footprint "eagle-import:SSO36_TDA7498ETR_STM")
      (fields (field (name "COPYRIGHT") "Copyright (C) 2018 Accelerated Designs. All rights reserved"))
      (libsource (lib "eagle-import") (part "TDA7498ETR"))
    )
    (comp (ref "C15")
      (value "100nF")
      (footprint "eagle-import:C0603")
      (libsource (lib "eagle-import") (part "C-EUC0603"))
    )
    (comp (ref "ESP")
      (value "ESP-WROOM-32")
      (footprint "eagle-import:ESP-WROOM-32")
      (libsource (lib "eagle-import") (part "ESP-WROOM-32"))
    )
    (comp (ref "IO4")
      (value "SMD2")
      (footprint "eagle-import:SMD1,27-2,54")
      (libsource (lib "eagle-import") (part "SMD2"))
    )
    (comp (ref "IO5")
      (value "SMD2")
      (footprint "eagle-import:SMD1,27-2,54")
      (libsource (lib "eagle-import") (part "SMD2"))
    )
    (comp (ref "IO14")
      (value "SMD2")
      (footprint "eagle-import:SMD1,27-2,54")
      (libsource (lib "eagle-import") (part "SMD2"))
    )
    (comp (ref "IO18")
      (value "SMD2")
      (footprint "eagle-import:SMD1,27-2,54")
      (libsource (lib "eagle-import") (part "SMD2"))
    )
    (comp (ref "IO19")
      (value "SMD2")
      (footprint "eagle-import:SMD1,27-2,54")
      (libsource (lib "eagle-import") (part "SMD2"))
    )
    (comp (ref "IO23")
      (value "SMD2")
      (footprint "eagle-import:SMD1,27-2,54")
      (libsource (lib "eagle-import") (part "SMD2"))
    )
    (comp (ref "IO25")
      (value "SMD2")
      (footprint "eagle-import:SMD1,27-2,54")
      (libsource (lib "eagle-import") (part "SMD2"))
    )
    (comp (ref "IO34")
      (value "SMD2")
      (footprint "eagle-import:SMD1,27-2,54")
      (libsource (lib "eagle-import") (part "SMD2"))
    )
    (comp (ref "IO35")
      (value "SMD2")
      (footprint "eagle-import:SMD1,27-2,54")
      (libsource (lib "eagle-import") (part "SMD2"))
    )
    (comp (ref "J3")
      (value "455-1750-1-ND")
      (footprint "eagle-import:1X03")
      (libsource (lib "eagle-import") (part "CONN_03"))
    )
    (comp (ref "J4")
      (value "455-1750-1-ND")
      (footprint "eagle-import:1X03")
      (libsource (lib "eagle-import") (part "CONN_03"))
    )
    (comp (ref "PAD1")
      (value "SMD2")
      (footprint "eagle-import:SMD1,27-2,54")
      (libsource (lib "eagle-import") (part "SMD2"))
    )
    (comp (ref "PAD2")
      (value "SMD2")
      (footprint "eagle-import:SMD1,27-2,54")
      (libsource (lib "eagle-import") (part "SMD2"))
    )
    (comp (ref "PAD3")
      (value "SMD2")
      (footprint "eagle-import:SMD1,27-2,54")
      (libsource (lib "eagle-import") (part "SMD2"))
    )
    (comp (ref "PAD4")
      (value "SMD2")
      (footprint "eagle-import:SMD1,27-2,54")
      (libsource (lib "eagle-import") (part "SMD2"))
    )
    (comp (ref "PAD5")
      (value "SMD2")
      (footprint "eagle-import:SMD1,27-2,54")
      (libsource (lib "eagle-import") (part "SMD2"))
    )
    (comp (ref "PAD6")
      (value "SMD2")
      (footprint "eagle-import:SMD1,27-2,54")
      (libsource (lib "eagle-import") (part "SMD2"))
    )
    (comp (ref "PAD7")
      (value "SMD2")
      (footprint "eagle-import:SMD1,27-2,54")
      (libsource (lib "eagle-import") (part "SMD2"))
    )
    (comp (ref "PAD8")
      (value "SMD2")
      (footprint "eagle-import:SMD1,27-2,54")
      (libsource (lib "eagle-import") (part "SMD2"))
    )
    (comp (ref "PAD9")
      (value "SMD2")
      (footprint "eagle-import:SMD1,27-2,54")
      (libsource (lib "eagle-import") (part "SMD2"))
    )
    (comp (ref "PAD10")
      (value "SMD2")
      (footprint "eagle-import:SMD1,27-2,54")
      (libsource (lib "eagle-import") (part "SMD2"))
    )
    (comp (ref "PAD11")
      (value "SMD2")
      (footprint "eagle-import:SMD1,27-2,54")
      (libsource (lib "eagle-import") (part "SMD2"))
    )
    (comp (ref "PAD12")
      (value "SMD2")
      (footprint "eagle-import:SMD1,27-2,54")
      (libsource (lib "eagle-import") (part "SMD2"))
    )
    (comp (ref "R8")
      (value "10kΩ")
      (footprint "eagle-import:R0603")
      (libsource (lib "eagle-import") (part "R-EU_R0603"))
    )
    (comp (ref "R13")
      (value "4.7kΩ")
      (footprint "eagle-import:R0603")
      (libsource (lib "eagle-import") (part "R-EU_R0603"))
    )
    (comp (ref "R14")
      (value "4.7kΩ")
      (footprint "eagle-import:R0603")
      (libsource (lib "eagle-import") (part "R-EU_R0603"))
    )
    (comp (ref "S1")
      (value "MOMENTARY-SWITCH-SPST-SMD-6.2MM-TALL")
      (footprint "eagle-import:TACTILE_SWITCH_SMD_6.2MM_TALL")
      (libsource (lib "eagle-import") (part "MOMENTARY-SWITCH-SPST-SMD-6.2MM-TALL"))
    )
    (comp (ref "S2")
      (value "MOMENTARY-SWITCH-SPST-SMD-6.2MM-TALL")
      (footprint "eagle-import:TACTILE_SWITCH_SMD_6.2MM_TALL")
      (libsource (lib "eagle-import") (part "MOMENTARY-SWITCH-SPST-SMD-6.2MM-TALL"))
    )
    (comp (ref "C67")
      (value "100nF")
      (footprint "eagle-import:C0603")
      (libsource (lib "eagle-import") (part "C-EUC0603"))
    )
    (comp (ref "C68")
      (value "10µF")
      (footprint "eagle-import:C1206K")
      (libsource (lib "eagle-import") (part "C-EUC1206K"))
    )
    (comp (ref "C69")
      (value "100nF")
      (footprint "eagle-import:C0603")
      (libsource (lib "eagle-import") (part "C-EUC0603"))
    )
    (comp (ref "C70")
      (value "100nF")
      (footprint "eagle-import:C0603")
      (libsource (lib "eagle-import") (part "C-EUC0603"))
    )
    (comp (ref "C71")
      (value "10µF")
      (footprint "eagle-import:C1206K")
      (libsource (lib "eagle-import") (part "C-EUC1206K"))
    )
    (comp (ref "C72")
      (value "100nF")
      (footprint "eagle-import:C0603")
      (libsource (lib "eagle-import") (part "C-EUC0603"))
    )
    (comp (ref "C73")
      (value "1000µF")
      (footprint "eagle-import:E7,5-16")
      (libsource (lib "eagle-import") (part "CPOL-EUE7.5-16"))
    )
    (comp (ref "C74")
      (value "1000µF")
      (footprint "eagle-import:E7,5-16")
      (libsource (lib "eagle-import") (part "CPOL-EUE7.5-16"))
    )
    (comp (ref "C75")
      (value "1µF")
      (footprint "eagle-import:C0603")
      (libsource (lib "eagle-import") (part "C-EUC0603"))
    )
    (comp (ref "C76")
      (value "100nF")
      (footprint "eagle-import:C0603")
      (libsource (lib "eagle-import") (part "C-EUC0603"))
    )
    (comp (ref "C77")
      (value "1µF")
      (footprint "eagle-import:C0603")
      (libsource (lib "eagle-import") (part "C-EUC0603"))
    )
    (comp (ref "C78")
      (value "100nF")
      (footprint "eagle-import:C0603")
      (libsource (lib "eagle-import") (part "C-EUC0603"))
    )
    (comp (ref "C79")
      (value "330pF")
      (footprint "eagle-import:C0603")
      (libsource (lib "eagle-import") (part "C-EUC0603"))
    )
    (comp (ref "C80")
      (value "220nF")
      (footprint "eagle-import:C0603")
      (libsource (lib "eagle-import") (part "C-EUC0603"))
    )
    (comp (ref "C81")
      (value "220nF")
      (footprint "eagle-import:C0603")
      (libsource (lib "eagle-import") (part "C-EUC0603"))
    )
    (comp (ref "C82")
      (value "220nF")
      (footprint "eagle-import:C0603")
      (libsource (lib "eagle-import") (part "C-EUC0603"))
    )
    (comp (ref "C83")
      (value "220nF")
      (footprint "eagle-import:C0603")
      (libsource (lib "eagle-import") (part "C-EUC0603"))
    )
    (comp (ref "C84")
      (value "1µF")
      (footprint "eagle-import:C3640")
      (libsource (lib "eagle-import") (part "C-EUC3640"))
    )
    (comp (ref "C85")
      (value "330pF")
      (footprint "eagle-import:C0603")
      (libsource (lib "eagle-import") (part "C-EUC0603"))
    )
    (comp (ref "C86")
      (value "1µF")
      (footprint "eagle-import:C3640")
      (libsource (lib "eagle-import") (part "C-EUC3640"))
    )
    (comp (ref "C87")
      (value "220nF")
      (footprint "eagle-import:C0603")
      (libsource (lib "eagle-import") (part "C-EUC0603"))
    )
    (comp (ref "C88")
      (value "220nF")
      (footprint "eagle-import:C0603")
      (libsource (lib "eagle-import") (part "C-EUC0603"))
    )
    (comp (ref "C89")
      (value "220nF")
      (footprint "eagle-import:C0603")
      (libsource (lib "eagle-import") (part "C-EUC0603"))
    )
    (comp (ref "C90")
      (value "220nF")
      (footprint "eagle-import:C0603")
      (libsource (lib "eagle-import") (part "C-EUC0603"))
    )
    (comp (ref "JP5")
      (value "JP1Q")
      (footprint "eagle-import:JP1")
      (libsource (lib "eagle-import") (part "JP1Q"))
    )
    (comp (ref "JP6")
      (value "JP1Q")
      (footprint "eagle-import:JP1")
      (libsource (lib "eagle-import") (part "JP1Q"))
    )
    (comp (ref "JP7")
      (value "JP1Q")
      (footprint "eagle-import:JP1")
      (libsource (lib "eagle-import") (part "JP1Q"))
    )
    (comp (ref "JP8")
      (value "JP1Q")
      (footprint "eagle-import:JP1")
      (libsource (lib "eagle-import") (part "JP1Q"))
    )
    (comp (ref "L7")
      (value "15µH")
      (footprint "eagle-import:INDUCTOR_SDR1307")
      (libsource (lib "eagle-import") (part "INDUCTOR-SDR13-27UH"))
    )
    (comp (ref "L8")
      (value "15µH")
      (footprint "eagle-import:INDUCTOR_SDR1307")
      (libsource (lib "eagle-import") (part "INDUCTOR-SDR13-27UH"))
    )
    (comp (ref "L9")
      (value "15µH")
      (footprint "eagle-import:INDUCTOR_SDR1307")
      (libsource (lib "eagle-import") (part "INDUCTOR-SDR13-27UH"))
    )
    (comp (ref "L10")
      (value "15µH")
      (footprint "eagle-import:INDUCTOR_SDR1307")
      (libsource (lib "eagle-import") (part "INDUCTOR-SDR13-27UH"))
    )
    (comp (ref "R40")
      (value "10kΩ")
      (footprint "eagle-import:R0603")
      (libsource (lib "eagle-import") (part "R-EU_R0603"))
    )
    (comp (ref "R41")
      (value "10kΩ")
      (footprint "eagle-import:R0603")
      (libsource (lib "eagle-import") (part "R-EU_R0603"))
    )
    (comp (ref "R42")
      (value "22Ω")
      (footprint "eagle-import:R0603")
      (libsource (lib "eagle-import") (part "R-EU_R0603"))
    )
    (comp (ref "R43")
      (value "47kΩ")
      (footprint "eagle-import:R0603")
      (libsource (lib "eagle-import") (part "R-EU_R0603"))
    )
    (comp (ref "R44")
      (value "10kΩ")
      (footprint "eagle-import:R0603")
      (libsource (lib "eagle-import") (part "R-EU_R0603"))
    )
    (comp (ref "R45")
      (value "100kΩ")
      (footprint "eagle-import:R0603")
      (libsource (lib "eagle-import") (part "R-EU_R0603"))
    )
    (comp (ref "R46")
      (value "100kΩ")
      (footprint "eagle-import:R0603")
      (libsource (lib "eagle-import") (part "R-EU_R0603"))
    )
    (comp (ref "R47")
      (value "100kΩ")
      (footprint "eagle-import:R0603")
      (libsource (lib "eagle-import") (part "R-EU_R0603"))
    )
    (comp (ref "R48")
      (value "22Ω")
      (footprint "eagle-import:R0603")
      (libsource (lib "eagle-import") (part "R-EU_R0603"))
    )
    (comp (ref "R49")
      (value "8Ω")
      (footprint "eagle-import:R0603")
      (libsource (lib "eagle-import") (part "R-EU_R0603"))
    )
    (comp (ref "R50")
      (value "8Ω")
      (footprint "eagle-import:R0603")
      (libsource (lib "eagle-import") (part "R-EU_R0603"))
    )
    (comp (ref "R51")
      (value "22Ω")
      (footprint "eagle-import:R0603")
      (libsource (lib "eagle-import") (part "R-EU_R0603"))
    )
    (comp (ref "R52")
      (value "8Ω")
      (footprint "eagle-import:R0603")
      (libsource (lib "eagle-import") (part "R-EU_R0603"))
    )
    (comp (ref "R53")
      (value "8Ω")
      (footprint "eagle-import:R0603")
      (libsource (lib "eagle-import") (part "R-EU_R0603"))
    )
    (comp (ref "SJ4") (value "SJ") (footprint "eagle-import:SJ") (libsource (lib "eagle-import") (part "SJ")))
    (comp (ref "SJ5") (value "SJ") (footprint "eagle-import:SJ") (libsource (lib "eagle-import") (part "SJ")))
    (comp (ref "U$3")
      (value "ATS-CPX030030030")
      (footprint "eagle-import:ATS-CPX030030030")
      (libsource (lib "eagle-import") (part "ATS-CPX030030030"))
    )
    (comp (ref "U3")
      (value "TDA7498ETR")
      (footprint "eagle-import:SSO36_TDA7498ETR_STM")
      (fields (field (name "COPYRIGHT") "Copyright (C) 2018 Accelerated Designs. All rights reserved"))
      (libsource (lib "eagle-import") (part "TDA7498ETR"))
    )
    (comp (ref "GND")
      (value "SMD5")
      (footprint "eagle-import:SMD2,54-5,08")
      (libsource (lib "eagle-import") (part "SMD5"))
    )
    (comp (ref "J1")
      (value "614004134726")
      (footprint "eagle-import:614004134726")
      (libsource (lib "eagle-import") (part "614004134726"))
    )
    (comp (ref "J2")
      (value "614004134726")
      (footprint "eagle-import:614004134726")
      (libsource (lib "eagle-import") (part "614004134726"))
    )
    (comp (ref "J5")
      (value "SJ1-3523N")
      (footprint "eagle-import:CUI_SJ1-3523N")
      (fields (field (name "MANUFACTURER") "CUI"))
      (libsource (lib "eagle-import") (part "SJ1-3523N"))
    )
    (comp (ref "OUT_A_+")
      (value "SMD2")
      (footprint "eagle-import:SMD1,27-2,54")
      (libsource (lib "eagle-import") (part "SMD2"))
    )
    (comp (ref "OUT_A_-")
      (value "SMD2")
      (footprint "eagle-import:SMD1,27-2,54")
      (libsource (lib "eagle-import") (part "SMD2"))
    )
    (comp (ref "OUT_B_+")
      (value "SMD2")
      (footprint "eagle-import:SMD1,27-2,54")
      (libsource (lib "eagle-import") (part "SMD2"))
    )
    (comp (ref "OUT_B_-")
      (value "SMD2")
      (footprint "eagle-import:SMD1,27-2,54")
      (libsource (lib "eagle-import") (part "SMD2"))
    )
    (comp (ref "OUT_C_+")
      (value "SMD2")
      (footprint "eagle-import:SMD1,27-2,54")
      (libsource (lib "eagle-import") (part "SMD2"))
    )
    (comp (ref "OUT_C_-")
      (value "SMD2")
      (footprint "eagle-import:SMD1,27-2,54")
      (libsource (lib "eagle-import") (part "SMD2"))
    )
    (comp (ref "OUT_D_+")
      (value "SMD2")
      (footprint "eagle-import:SMD1,27-2,54")
      (libsource (lib "eagle-import") (part "SMD2"))
    )
    (comp (ref "OUT_D_-")
      (value "SMD2")
      (footprint "eagle-import:SMD1,27-2,54")
      (libsource (lib "eagle-import") (part "SMD2"))
    )
    (comp (ref "R9")
      (value "TRIM_EU-CIP20C-6MM")
      (footprint "eagle-import:CIP20C-6MM")
      (libsource (lib "eagle-import") (part "TRIM_EU-CIP20C-6MM"))
    )
    (comp (ref "R10")
      (value "TRIM_EU-CIP20C-6MM")
      (footprint "eagle-import:CIP20C-6MM")
      (libsource (lib "eagle-import") (part "TRIM_EU-CIP20C-6MM"))
    )
    (comp (ref "R11")
      (value "TRIM_EU-CIP20C-6MM")
      (footprint "eagle-import:CIP20C-6MM")
      (libsource (lib "eagle-import") (part "TRIM_EU-CIP20C-6MM"))
    )
    (comp (ref "R12")
      (value "TRIM_EU-CIP20C-6MM")
      (footprint "eagle-import:CIP20C-6MM")
      (libsource (lib "eagle-import") (part "TRIM_EU-CIP20C-6MM"))
    )
    (comp (ref "U$1")
      (value "XT60")
      (footprint "eagle-import:XT60")
      (libsource (lib "eagle-import") (part "XT60"))
    )
    (comp (ref "VIN")
      (value "SMD5")
      (footprint "eagle-import:SMD2,54-5,08")
      (libsource (lib "eagle-import") (part "SMD5"))
    )
    (comp (ref "X1")
      (value "MKDSN1,5/2-5,08")
      (footprint "eagle-import:MKDSN1,5_2-5,08")
      (libsource (lib "eagle-import") (part "MKDSN1,5/2-5,08"))
    )
  )
  (nets
    (net (code "1") (name "+3V3") (class "Default")
      (node (ref "C13") (pin "1") (pinfunction "1_1") (pintype "passive"))
      (node (ref "C14") (pin "1") (pinfunction "1_1") (pintype "passive"))
      (node (ref "C15") (pin "2") (pinfunction "2_2") (pintype "passive"))
      (node (ref "C18") (pin "1") (pinfunction "1_1") (pintype "passive"))
      (node (ref "C19") (pin "1") (pinfunction "1_1") (pintype "passive"))
      (node (ref "C20") (pin "1") (pinfunction "1_1") (pintype "passive"))
      (node (ref "C21") (pin "1") (pinfunction "1_1") (pintype "passive"))
      (node (ref "C23") (pin "1") (pinfunction "1_1") (pintype "passive"))
      (node (ref "C24") (pin "1") (pinfunction "1_1") (pintype "passive"))
      (node (ref "C33") (pin "2") (pinfunction "2_2") (pintype "passive"))
      (node (ref "ESP") (pin "2") (pinfunction "3V3_2") (pintype "power_in"))
      (node (ref "IC1") (pin "2") (pinfunction "VOUT_2") (pintype "output"))
      (node (ref "PAD10") (pin "1") (pinfunction "P_1") (pintype "passive"))
      (node (ref "PAD2") (pin "1") (pinfunction "P_1") (pintype "passive"))
      (node (ref "PAD4") (pin "1") (pinfunction "P_1") (pintype "passive"))
      (node (ref "Q1") (pin "3") (pinfunction "E_3") (pintype "passive"))
      (node (ref "R10") (pin "E") (pinfunction "E_E") (pintype "passive"))
      (node (ref "R11") (pin "E") (pinfunction "E_E") (pintype "passive"))
      (node (ref "R12") (pin "E") (pinfunction "E_E") (pintype "passive"))
      (node (ref "R13") (pin "1") (pinfunction "1_1") (pintype "passive"))
      (node (ref "R14") (pin "1") (pinfunction "1_1") (pintype "passive"))
      (node (ref "R15") (pin "2") (pinfunction "2_2") (pintype "passive"))
      (node (ref "R16") (pin "2") (pinfunction "2_2") (pintype "passive"))
      (node (ref "R21") (pin "1") (pinfunction "1_1") (pintype "passive"))
      (node (ref "R31") (pin "2") (pinfunction "2_2") (pintype "passive"))
      (node (ref "R45") (pin "2") (pinfunction "2_2") (pintype "passive"))
      (node (ref "R8") (pin "2") (pinfunction "2_2") (pintype "passive"))
      (node (ref "R9") (pin "E") (pinfunction "E_E") (pintype "passive"))
      (node (ref "SJ1") (pin "3") (pinfunction "3_3") (pintype "passive"))
      (node (ref "U1") (pin "18") (pinfunction "IOVDD_18") (pintype "power_in"))
      (node (ref "U1") (pin "34") (pinfunction "PVDD_34") (pintype "power_in"))
      (node (ref "U1") (pin "36") (pinfunction "AVDD_2_36") (pintype "power_in"))
      (node (ref "U1") (pin "39") (pinfunction "PLL_MODE1_39") (pintype "input"))
      (node (ref "U1") (pin "48") (pinfunction "AVDD_48") (pintype "power_in"))
    )
    (net (code "2") (name "+5V") (class "Default")
      (node (ref "C11") (pin "+") (pinfunction "+_+") (pintype "passive"))
      (node (ref "J1") (pin "1") (pinfunction "VBUS_1") (pintype "bidirectional"))
      (node (ref "J2") (pin "1") (pinfunction "VBUS_1") (pintype "bidirectional"))
      (node (ref "L2") (pin "P$2") (pinfunction "2_P$2") (pintype "passive"))
      (node (ref "PAD5") (pin "1") (pinfunction "P_1") (pintype "passive"))
      (node (ref "PAD6") (pin "1") (pinfunction "P_1") (pintype "passive"))
      (node (ref "PAD7") (pin "1") (pinfunction "P_1") (pintype "passive"))
      (node (ref "R5") (pin "2") (pinfunction "2_2") (pintype "passive"))
      (node (ref "R7") (pin "2") (pinfunction "2_2") (pintype "passive"))
      (node (ref "REG2") (pin "6") (pinfunction "VOS_6") (pintype "input"))
    )
    (net (code "3") (name "+12V") (class "Default")
      (node (ref "C10") (pin "+") (pinfunction "+_+") (pintype "passive"))
      (node (ref "C12") (pin "1") (pinfunction "1_1") (pintype "passive"))
      (node (ref "C6") (pin "+") (pinfunction "+_+") (pintype "passive"))
      (node (ref "C9") (pin "1") (pinfunction "1_1") (pintype "passive"))
      (node (ref "IC1") (pin "3") (pinfunction "VIN_3") (pintype "input"))
      (node (ref "L1") (pin "P$2") (pinfunction "2_P$2") (pintype "passive"))
      (node (ref "R3") (pin "2") (pinfunction "2_2") (pintype "passive"))
      (node (ref "REG2") (pin "1") (pinfunction "VIN_1") (pintype "power_in"))
      (node (ref "REG2") (pin "8") (pinfunction "EN_8") (pintype "input"))
      (node (ref "X1") (pin "1") (pinfunction "KL_1") (pintype "passive"))
    )
    (net (code "4") (name "AMP1_GAIN") (class "Default")
      (node (ref "JP1") (pin "2") (pinfunction "2_2") (pintype "passive"))
      (node (ref "JP2") (pin "2") (pinfunction "2_2") (pintype "passive"))
      (node (ref "JP3") (pin "2") (pinfunction "2_2") (pintype "passive"))
      (node (ref "JP4") (pin "2") (pinfunction "2_2") (pintype "passive"))
      (node (ref "U2") (pin "30") (pinfunction "GAIN_30") (pintype "passive"))
    )
    (net (code "5") (name "AMP1_IN_A") (class "Default")
      (node (ref "SJ2") (pin "2") (pinfunction "2_2") (pintype "passive"))
      (node (ref "U2") (pin "22") (pinfunction "INPA_22") (pintype "input"))
    )
    (net (code "6") (name "AMP1_IN_B") (class "Default")
      (node (ref "SJ3") (pin "2") (pinfunction "2_2") (pintype "passive"))
      (node (ref "U2") (pin "32") (pinfunction "INPB_32") (pintype "input"))
    )
    (net (code "7") (name "AMP1_MUTE") (class "Default")
      (node (ref "ESP") (pin "28") (pinfunction "IO17_28") (pintype "bidirectional"))
      (node (ref "R27") (pin "2") (pinfunction "2_2") (pintype "passive"))
      (node (ref "U2") (pin "21") (pinfunction "MUTE_21") (pintype "passive"))
    )
    (net (code "8") (name "AMP1_OUTA_N") (class "Default")
      (node (ref "C55") (pin "1") (pinfunction "1_1") (pintype "passive"))
      (node (ref "L4") (pin "P$1") (pinfunction "1_P$1") (pintype "passive"))
      (node (ref "U2") (pin "10") (pinfunction "OUTNA_2_10") (pintype "output"))
      (node (ref "U2") (pin "11") (pinfunction "OUTNA_11") (pintype "output"))
    )
    (net (code "9") (name "AMP1_OUTA_P") (class "Default")
      (node (ref "L3") (pin "P$1") (pinfunction "1_P$1") (pintype "passive"))
      (node (ref "R34") (pin "2") (pinfunction "2_2") (pintype "passive"))
      (node (ref "U2") (pin "16") (pinfunction "OUTPA_2_16") (pintype "output"))
      (node (ref "U2") (pin "17") (pinfunction "OUTPA_17") (pintype "output"))
    )
    (net (code "10") (name "AMP1_OUTB_N") (class "Default")
      (node (ref "C61") (pin "1") (pinfunction "1_1") (pintype "passive"))
      (node (ref "L6") (pin "P$1") (pinfunction "1_P$1") (pintype "passive"))
      (node (ref "U2") (pin "8") (pinfunction "OUTNB_2_8") (pintype "output"))
      (node (ref "U2") (pin "9") (pinfunction "OUTNB_9") (pintype "output"))
    )
    (net (code "11") (name "AMP1_PGND") (class "Default")
      (node (ref "C45") (pin "1") (pinfunction "1_1") (pintype "passive"))
      (node (ref "U2") (pin "18") (pinfunction "PGND_18") (pintype "passive"))
    )
    (net (code "12") (name "AMP1_ROSC") (class "Default")
      (node (ref "C48") (pin "2") (pinfunction "2_2") (pintype "passive"))
      (node (ref "R30") (pin "2") (pinfunction "2_2") (pintype "passive"))
      (node (ref "U2") (pin "24") (pinfunction "ROSC_24") (pintype "passive"))
    )
    (net (code "13") (name "AMP1_STANDBY") (class "Default")
      (node (ref "ESP") (pin "27") (pinfunction "IO16_27") (pintype "bidirectional"))
      (node (ref "R26") (pin "2") (pinfunction "2_2") (pintype "passive"))
      (node (ref "U2") (pin "20") (pinfunction "STBY_20") (pintype "passive"))
    )
    (net (code "14") (name "AMP1_SYNCLK") (class "Default")
      (node (ref "U2") (pin "25") (pinfunction "SYNCLK_25") (pintype "passive"))
    )
    (net (code "15") (name "AMP1_VDDPW") (class "Default")
      (node (ref "C45") (pin "2") (pinfunction "2_2") (pintype "passive"))
      (node (ref "R28") (pin "2") (pinfunction "2_2") (pintype "passive"))
      (node (ref "U2") (pin "19") (pinfunction "VDDPW_19") (pintype "power_in"))
    )
    (net (code "16") (name "AMP1_VDDS") (class "Default")
      (node (ref "C46") (pin "1") (pinfunction "1_1") (pintype "passive"))
      (node (ref "JP4") (pin "1") (pinfunction "1_1") (pintype "passive"))
      (node (ref "R28") (pin "1") (pinfunction "1_1") (pintype "passive"))
      (node (ref "R29") (pin "2") (pinfunction "2_2") (pintype "passive"))
      (node (ref "U2") (pin "26") (pinfunction "VDDS_26") (pintype "power_in"))
    )
    (net (code "17") (name "AMP1_VREF") (class "Default")
      (node (ref "C47") (pin "1") (pinfunction "1_1") (pintype "passive"))
      (node (ref "U2") (pin "34") (pinfunction "VREF_34") (pintype "power_in"))
    )
    (net (code "18") (name "AMP1_VSS") (class "Default")
      (node (ref "C43") (pin "1") (pinfunction "1_1") (pintype "passive"))
      (node (ref "U2") (pin "36") (pinfunction "VSS_36") (pintype "passive"))
    )
    (net (code "19") (name "AMP2_GAIN") (class "Default")
      (node (ref "JP5") (pin "2") (pinfunction "2_2") (pintype "passive"))
      (node (ref "JP6") (pin "2") (pinfunction "2_2") (pintype "passive"))
      (node (ref "JP7") (pin "2") (pinfunction "2_2") (pintype "passive"))
      (node (ref "JP8") (pin "2") (pinfunction "2_2") (pintype "passive"))
      (node (ref "U3") (pin "30") (pinfunction "GAIN_30") (pintype "passive"))
    )
    (net (code "20") (name "AMP2_IN_A") (class "Default")
      (node (ref "SJ5") (pin "2") (pinfunction "2_2") (pintype "passive"))
      (node (ref "U3") (pin "22") (pinfunction "INPA_22") (pintype "input"))
    )
    (net (code "21") (name "AMP2_IN_B") (class "Default")
      (node (ref "SJ4") (pin "2") (pinfunction "2_2") (pintype "passive"))
      (node (ref "U3") (pin "32") (pinfunction "INPB_32") (pintype "input"))
    )
    (net (code "22") (name "AMP2_MUTE") (class "Default")
      (node (ref "ESP") (pin "9") (pinfunction "IO33_9") (pintype "bidirectional"))
      (node (ref "R41") (pin "2") (pinfunction "2_2") (pintype "passive"))
      (node (ref "U3") (pin "21") (pinfunction "MUTE_21") (pintype "passive"))
    )
    (net (code "23") (name "AMP2_OUTA_N") (class "Default")
      (node (ref "C79") (pin "1") (pinfunction "1_1") (pintype "passive"))
      (node (ref "L8") (pin "P$1") (pinfunction "1_P$1") (pintype "passive"))
      (node (ref "U3") (pin "10") (pinfunction "OUTNA_2_10") (pintype "output"))
      (node (ref "U3") (pin "11") (pinfunction "OUTNA_11") (pintype "output"))
    )
    (net (code "24") (name "AMP2_OUTA_P") (class "Default")
      (node (ref "L7") (pin "P$1") (pinfunction "1_P$1") (pintype "passive"))
      (node (ref "R48") (pin "2") (pinfunction "2_2") (pintype "passive"))
      (node (ref "U3") (pin "16") (pinfunction "OUTPA_2_16") (pintype "output"))
      (node (ref "U3") (pin "17") (pinfunction "OUTPA_17") (pintype "output"))
    )
    (net (code "25") (name "AMP2_OUTB_N") (class "Default")
      (node (ref "C85") (pin "1") (pinfunction "1_1") (pintype "passive"))
      (node (ref "L10") (pin "P$1") (pinfunction "1_P$1") (pintype "passive"))
      (node (ref "U3") (pin "8") (pinfunction "OUTNB_2_8") (pintype "output"))
      (node (ref "U3") (pin "9") (pinfunction "OUTNB_9") (pintype "output"))
    )
    (net (code "26") (name "AMP2_OUTB_P") (class "Default")
      (node (ref "L9") (pin "P$1") (pinfunction "1_P$1") (pintype "passive"))
      (node (ref "R51") (pin "2") (pinfunction "2_2") (pintype "passive"))
      (node (ref "U3") (pin "2") (pinfunction "OUTPB_2_2") (pintype "output"))
      (node (ref "U3") (pin "3") (pinfunction "OUTPB_3") (pintype "output"))
    )
    (net (code "27") (name "AMP2_PGND") (class "Default")
      (node (ref "C69") (pin "1") (pinfunction "1_1") (pintype "passive"))
      (node (ref "U3") (pin "18") (pinfunction "PGND_18") (pintype "passive"))
    )
    (net (code "28") (name "AMP2_ROSC") (class "Default")
      (node (ref "C72") (pin "2") (pinfunction "2_2") (pintype "passive"))
      (node (ref "R44") (pin "2") (pinfunction "2_2") (pintype "passive"))
      (node (ref "U3") (pin "24") (pinfunction "ROSC_24") (pintype "passive"))
    )
    (net (code "29") (name "AMP2_STANDBY") (class "Default")
      (node (ref "ESP") (pin "8") (pinfunction "IO32_8") (pintype "bidirectional"))
      (node (ref "R40") (pin "2") (pinfunction "2_2") (pintype "passive"))
      (node (ref "U3") (pin "20") (pinfunction "STBY_20") (pintype "passive"))
    )
    (net (code "30") (name "AMP2_SYNCLK") (class "Default")
      (node (ref "U3") (pin "25") (pinfunction "SYNCLK_25") (pintype "passive"))
    )
    (net (code "31") (name "AMP2_VDDPW") (class "Default")
      (node (ref "C69") (pin "2") (pinfunction "2_2") (pintype "passive"))
      (node (ref "R42") (pin "2") (pinfunction "2_2") (pintype "passive"))
      (node (ref "U3") (pin "19") (pinfunction "VDDPW_19") (pintype "power_in"))
    )
    (net (code "32") (name "AMP2_VDDS") (class "Default")
      (node (ref "C70") (pin "1") (pinfunction "1_1") (pintype "passive"))
      (node (ref "JP8") (pin "1") (pinfunction "1_1") (pintype "passive"))
      (node (ref "R42") (pin "1") (pinfunction "1_1") (pintype "passive"))
      (node (ref "R43") (pin "2") (pinfunction "2_2") (pintype "passive"))
      (node (ref "U3") (pin "26") (pinfunction "VDDS_26") (pintype "power_in"))
    )
    (net (code "33") (name "AMP2_VREF") (class "Default")
      (node (ref "C71") (pin "1") (pinfunction "1_1") (pintype "passive"))
      (node (ref "U3") (pin "34") (pinfunction "VREF_34") (pintype "power_in"))
    )
    (net (code "34") (name "AMP2_VSS") (class "Default")
      (node (ref "C67") (pin "1") (pinfunction "1_1") (pintype "passive"))
      (node (ref "U3") (pin "36") (pinfunction "VSS_36") (pintype "passive"))
    )
    (net (code "35") (name "AMP3_OUTB_P") (class "Default")
      (node (ref "L5") (pin "P$1") (pinfunction "1_P$1") (pintype "passive"))
      (node (ref "R37") (pin "2") (pinfunction "2_2") (pintype "passive"))
      (node (ref "U2") (pin "2") (pinfunction "OUTPB_2_2") (pintype "output"))
      (node (ref "U2") (pin "3") (pinfunction "OUTPB_3") (pintype "output"))
    )
    (net (code "36") (name "A_LINE_A") (class "Default")
      (node (ref "C36") (pin "1") (pinfunction "1_1") (pintype "passive"))
      (node (ref "R22") (pin "1") (pinfunction "1_1") (pintype "passive"))
      (node (ref "SJ3") (pin "1") (pinfunction "1_1") (pintype "passive"))
      (node (ref "SJ6") (pin "2") (pinfunction "2_2") (pintype "passive"))
    )
    (net (code "37") (name "A_LINE_B") (class "Default")
      (node (ref "C38") (pin "1") (pinfunction "1_1") (pintype "passive"))
      (node (ref "R23") (pin "1") (pinfunction "1_1") (pintype "passive"))
      (node (ref "SJ2") (pin "1") (pinfunction "1_1") (pintype "passive"))
      (node (ref "SJ7") (pin "2") (pinfunction "2_2") (pintype "passive"))
    )
    (net (code "38") (name "A_LINE_C") (class "Default")
      (node (ref "C40") (pin "1") (pinfunction "1_1") (pintype "passive"))
      (node (ref "R24") (pin "1") (pinfunction "1_1") (pintype "passive"))
      (node (ref "SJ4") (pin "1") (pinfunction "1_1") (pintype "passive"))
      (node (ref "SJ8") (pin "2") (pinfunction "2_2") (pintype "passive"))
    )
    (net (code "39") (name "A_LINE_D") (class "Default")
      (node (ref "C42") (pin "1") (pinfunction "1_1") (pintype "passive"))
      (node (ref "R25") (pin "1") (pinfunction "1_1") (pintype "passive"))
      (node (ref "SJ5") (pin "1") (pinfunction "1_1") (pintype "passive"))
      (node (ref "SJ9") (pin "2") (pinfunction "2_2") (pintype "passive"))
    )
    (net (code "40") (name "DSP_DVDD") (class "Default")
      (node (ref "C16") (pin "1") (pinfunction "1_1") (pintype "passive"))
      (node (ref "C17") (pin "1") (pinfunction "1_1") (pintype "passive"))
      (node (ref "C22") (pin "1") (pinfunction "1_1") (pintype "passive"))
      (node (ref "Q1") (pin "2") (pinfunction "C_2") (pintype "passive"))
      (node (ref "Q1") (pin "4") (pinfunction "C_4") (pintype "passive"))
      (node (ref "U1") (pin "13") (pinfunction "DVDD_2_13") (pintype "power_in"))
      (node (ref "U1") (pin "24") (pinfunction "DVDD_24") (pintype "power_in"))
    )
    (net (code "41") (name "DSP_IN_BCLK") (class "Default")
      (node (ref "ESP") (pin "12") (pinfunction "IO27_12") (pintype "bidirectional"))
      (node (ref "U1") (pin "9") (pinfunction "MP5_9") (pintype "bidirectional"))
    )
    (net (code "42") (name "DSP_IN_LRCLK") (class "Default")
      (node (ref "ESP") (pin "16") (pinfunction "IO13_16") (pintype "bidirectional"))
      (node (ref "U1") (pin "8") (pinfunction "MP4_8") (pintype "bidirectional"))
    )
    (net (code "43") (name "DSP_IN_SDATA0") (class "Default")
      (node (ref "ESP") (pin "11") (pinfunction "IO26_11") (pintype "bidirectional"))
      (node (ref "U1") (pin "10") (pinfunction "MP1_10") (pintype "bidirectional"))
    )
    (net (code "44") (name "DSP_IN_SDATA1") (class "Default")
      (node (ref "U1") (pin "11") (pinfunction "MP0_11") (pintype "bidirectional"))
    )
    (net (code "45") (name "DSP_MCLKI") (class "Default")
      (node (ref "C26") (pin "1") (pinfunction "1_1") (pintype "passive"))
      (node (ref "Q2") (pin "1") (pinfunction "1_1") (pintype "passive"))
      (node (ref "U1") (pin "32") (pinfunction "MCLKI_32") (pintype "input"))
    )
    (net (code "46") (name "DSP_OSCO") (class "Default")
      (node (ref "R20") (pin "1") (pinfunction "1_1") (pintype "passive"))
      (node (ref "U1") (pin "31") (pinfunction "OSCO_31") (pintype "output"))
    )
    (net (code "47") (name "DSP_OUT_BCLK") (class "Default")
      (node (ref "U1") (pin "19") (pinfunction "MP11_19") (pintype "bidirectional"))
    )
    (net (code "48") (name "DSP_OUT_LRCLK") (class "Default")
      (node (ref "U1") (pin "16") (pinfunction "MP10_16") (pintype "bidirectional"))
    )
    (net (code "49") (name "DSP_OUT_SDATA0") (class "Default")
      (node (ref "U1") (pin "15") (pinfunction "MP6_15") (pintype "bidirectional"))
    )
    (net (code "50") (name "DSP_OUT_SDATA1") (class "Default")
      (node (ref "U1") (pin "14") (pinfunction "MP7_14") (pintype "bidirectional"))
    )
    (net (code "51") (name "DSP_RESET") (class "Default")
      (node (ref "ESP") (pin "14") (pinfunction "IO12_14") (pintype "bidirectional"))
      (node (ref "J6") (pin "1") (pinfunction "1_1") (pintype "passive"))
      (node (ref "R16") (pin "1") (pinfunction "1_1") (pintype "passive"))
      (node (ref "U1") (pin "5") (pinfunction "~{RESET}_5") (pintype "input"))
    )
    (net (code "52") (name "DSP_SELFBOOT") (class "Default")
      (node (ref "SJ1") (pin "2") (pinfunction "2_2") (pintype "passive"))
      (node (ref "U1") (pin "6") (pinfunction "SELFBOOT_6") (pintype "input"))
    )
    (net (code "53") (name "DSP_VDRIVE") (class "Default")
      (node (ref "Q1") (pin "1") (pinfunction "B_1") (pintype "passive"))
      (node (ref "R15") (pin "1") (pinfunction "1_1") (pintype "passive"))
      (node (ref "U1") (pin "17") (pinfunction "VDRIVE_17") (pintype "output"))
    )
    (net (code "54") (name "DSP_VOUT0") (class "Default")
      (node (ref "C35") (pin "+") (pinfunction "+_+") (pintype "passive"))
      (node (ref "SJ6") (pin "1") (pinfunction "1_1") (pintype "passive"))
      (node (ref "U1") (pin "46") (pinfunction "VOUT0_46") (pintype "output"))
    )
    (net (code "55") (name "DSP_VOUT1") (class "Default")
      (node (ref "C37") (pin "+") (pinfunction "+_+") (pintype "passive"))
      (node (ref "SJ7") (pin "1") (pinfunction "1_1") (pintype "passive"))
      (node (ref "U1") (pin "45") (pinfunction "VOUT1_45") (pintype "output"))
    )
    (net (code "56") (name "DSP_VOUT2") (class "Default")
      (node (ref "C39") (pin "+") (pinfunction "+_+") (pintype "passive"))
      (node (ref "SJ8") (pin "1") (pinfunction "1_1") (pintype "passive"))
      (node (ref "U1") (pin "44") (pinfunction "VOUT2_44") (pintype "output"))
    )
    (net (code "57") (name "DSP_VOUT3") (class "Default")
      (node (ref "C41") (pin "+") (pinfunction "+_+") (pintype "passive"))
      (node (ref "SJ9") (pin "1") (pinfunction "1_1") (pintype "passive"))
      (node (ref "U1") (pin "43") (pinfunction "VOUT3_43") (pintype "output"))
    )
    (net (code "58") (name "ESP_CLK") (class "Default")
      (node (ref "ESP") (pin "20") (pinfunction "CLK_20") (pintype "bidirectional"))
    )
    (net (code "59") (name "ESP_CMD") (class "Default")
      (node (ref "ESP") (pin "19") (pinfunction "CMD_19") (pintype "bidirectional"))
    )
    (net (code "60") (name "ESP_EN") (class "Default")
      (node (ref "ESP") (pin "3") (pinfunction "EN_3") (pintype "input"))
      (node (ref "R8") (pin "1") (pinfunction "1_1") (pintype "passive"))
      (node (ref "S1") (pin "B2") (pinfunction "2_B2") (pintype "passive"))
    )
    (net (code "61") (name "ESP_IO0") (class "Default")
      (node (ref "ESP") (pin "25") (pinfunction "IO0_25") (pintype "bidirectional"))
      (node (ref "S2") (pin "A2") (pinfunction "1_A2") (pintype "passive"))
    )
    (net (code "62") (name "ESP_IO2") (class "Default")
      (node (ref "ESP") (pin "24") (pinfunction "IO2_24") (pintype "bidirectional"))
    )
    (net (code "63") (name "ESP_IO4") (class "Default")
      (node (ref "ESP") (pin "26") (pinfunction "IO4_26") (pintype "bidirectional"))
      (node (ref "IO4") (pin "1") (pinfunction "P_1") (pintype "passive"))
    )
    (net (code "64") (name "ESP_IO5") (class "Default")
      (node (ref "ESP") (pin "29") (pinfunction "IO5_29") (pintype "bidirectional"))
      (node (ref "IO5") (pin "1") (pinfunction "P_1") (pintype "passive"))
    )
    (net (code "65") (name "ESP_IO14") (class "Default")
      (node (ref "ESP") (pin "13") (pinfunction "IO14_13") (pintype "bidirectional"))
      (node (ref "IO14") (pin "1") (pinfunction "P_1") (pintype "passive"))
    )
    (net (code "66") (name "ESP_IO15") (class "Default")
      (node (ref "ESP") (pin "23") (pinfunction "IO15_23") (pintype "bidirectional"))
    )
    (net (code "67") (name "ESP_IO18") (class "Default")
      (node (ref "ESP") (pin "30") (pinfunction "IO18_30") (pintype "bidirectional"))
      (node (ref "IO18") (pin "1") (pinfunction "P_1") (pintype "passive"))
    )
    (net (code "68") (name "ESP_IO19") (class "Default")
      (node (ref "ESP") (pin "31") (pinfunction "IO19_31") (pintype "bidirectional"))
      (node (ref "IO19") (pin "1") (pinfunction "P_1") (pintype "passive"))
    )
    (net (code "69") (name "ESP_IO23") (class "Default")
      (node (ref "ESP") (pin "37") (pinfunction "IO23_37") (pintype "bidirectional"))
      (node (ref "IO23") (pin "1") (pinfunction "P_1") (pintype "passive"))
    )
    (net (code "70") (name "ESP_IO25") (class "Default")
      (node (ref "ESP") (pin "10") (pinfunction "IO25_10") (pintype "bidirectional"))
      (node (ref "IO25") (pin "1") (pinfunction "P_1") (pintype "passive"))
    )
    (net (code "71") (name "ESP_IO34") (class "Default")
      (node (ref "ESP") (pin "6") (pinfunction "IO34_6") (pintype "bidirectional"))
      (node (ref "IO34") (pin "1") (pinfunction "P_1") (pintype "passive"))
    )
    (net (code "72") (name "ESP_IO35") (class "Default")
      (node (ref "ESP") (pin "7") (pinfunction "IO35_7") (pintype "bidirectional"))
      (node (ref "IO35") (pin "1") (pinfunction "P_1") (pintype "passive"))
    )
    (net (code "73") (name "ESP_RXD0") (class "Default")
      (node (ref "ESP") (pin "34") (pinfunction "RXD0_34") (pintype "bidirectional"))
      (node (ref "J3") (pin "2") (pinfunction "2_2") (pintype "passive"))
    )
    (net (code "74") (name "ESP_SD0") (class "Default")
      (node (ref "ESP") (pin "21") (pinfunction "SD0_21") (pintype "bidirectional"))
    )
    (net (code "75") (name "ESP_SD1") (class "Default")
      (node (ref "ESP") (pin "22") (pinfunction "SD1_22") (pintype "bidirectional"))
    )
    (net (code "76") (name "ESP_SD2") (class "Default")
      (node (ref "ESP") (pin "17") (pinfunction "SD2_17") (pintype "bidirectional"))
    )
    (net (code "77") (name "ESP_SD3") (class "Default")
      (node (ref "ESP") (pin "18") (pinfunction "SD3_18") (pintype "bidirectional"))
    )
    (net (code "78") (name "ESP_SENSOR_VN") (class "Default")
      (node (ref "ESP") (pin "5") (pinfunction "SENSOR_VN_5") (pintype "bidirectional"))
    )
    (net (code "79") (name "ESP_SENSOR_VP") (class "Default")
      (node (ref "ESP") (pin "4") (pinfunction "SENSOR_VP_4") (pintype "bidirectional"))
    )
    (net (code "80") (name "ESP_TXD0") (class "Default")
      (node (ref "ESP") (pin "35") (pinfunction "TXD0_35") (pintype "bidirectional"))
      (node (ref "J3") (pin "1") (pinfunction "1_1") (pintype "passive"))
    )
    (net (code "81") (name "GND") (class "Default")
      (node (ref "C1") (pin "-") (pinfunction "-_-") (pintype "passive"))
      (node (ref "C10") (pin "-") (pinfunction "-_-") (pintype "passive"))
      (node (ref "C11") (pin "-") (pinfunction "-_-") (pintype "passive"))
      (node (ref "C12") (pin "2") (pinfunction "2_2") (pintype "passive"))
      (node (ref "C13") (pin "2") (pinfunction "2_2") (pintype "passive"))
      (node (ref "C14") (pin "2") (pinfunction "2_2") (pintype "passive"))
      (node (ref "C15") (pin "1") (pinfunction "1_1") (pintype "passive"))
      (node (ref "C16") (pin "2") (pinfunction "2_2") (pintype "passive"))
      (node (ref "C17") (pin "2") (pinfunction "2_2") (pintype "passive"))
      (node (ref "C18") (pin "2") (pinfunction "2_2") (pintype "passive"))
      (node (ref "C19") (pin "2") (pinfunction "2_2") (pintype "passive"))
      (node (ref "C2") (pin "-") (pinfunction "-_-") (pintype "passive"))
      (node (ref "C20") (pin "2") (pinfunction "2_2") (pintype "passive"))
      (node (ref "C21") (pin "2") (pinfunction "2_2") (pintype "passive"))
      (node (ref "C22") (pin "2") (pinfunction "2_2") (pintype "passive"))
      (node (ref "C23") (pin "2") (pinfunction "2_2") (pintype "passive"))
      (node (ref "C24") (pin "2") (pinfunction "2_2") (pintype "passive"))
      (node (ref "C25") (pin "2") (pinfunction "2_2") (pintype "passive"))
      (node (ref "C26") (pin "2") (pinfunction "2_2") (pintype "passive"))
      (node (ref "C27") (pin "1") (pinfunction "1_1") (pintype "passive"))
      (node (ref "C28") (pin "1") (pinfunction "1_1") (pintype "passive"))
      (node (ref "C29") (pin "1") (pinfunction "1_1") (pintype "passive"))
      (node (ref "C3") (pin "2") (pinfunction "2_2") (pintype "passive"))
      (node (ref "C30") (pin "1") (pinfunction "1_1") (pintype "passive"))
      (node (ref "C31") (pin "1") (pinfunction "1_1") (pintype "passive"))
      (node (ref "C32") (pin "1") (pinfunction "1_1") (pintype "passive"))
      (node (ref "C36") (pin "2") (pinfunction "2_2") (pintype "passive"))
      (node (ref "C38") (pin "2") (pinfunction "2_2") (pintype "passive"))
      (node (ref "C4") (pin "2") (pinfunction "2_2") (pintype "passive"))
      (node (ref "C40") (pin "2") (pinfunction "2_2") (pintype "passive"))
      (node (ref "C42") (pin "2") (pinfunction "2_2") (pintype "passive"))
      (node (ref "C44") (pin "2") (pinfunction "2_2") (pintype "passive"))
      (node (ref "C46") (pin "2") (pinfunction "2_2") (pintype "passive"))
      (node (ref "C47") (pin "2") (pinfunction "2_2") (pintype "passive"))
      (node (ref "C48") (pin "1") (pinfunction "1_1") (pintype "passive"))
      (node (ref "C49") (pin "-") (pinfunction "-_-") (pintype "passive"))
      (node (ref "C50") (pin "-") (pinfunction "-_-") (pintype "passive"))
      (node (ref "C51") (pin "2") (pinfunction "2_2") (pintype "passive"))
      (node (ref "C52") (pin "2") (pinfunction "2_2") (pintype "passive"))
      (node (ref "C53") (pin "2") (pinfunction "2_2") (pintype "passive"))
      (node (ref "C54") (pin "2") (pinfunction "2_2") (pintype "passive"))
      (node (ref "C56") (pin "1") (pinfunction "1_1") (pintype "passive"))
      (node (ref "C57") (pin "2") (pinfunction "2_2") (pintype "passive"))
      (node (ref "C58") (pin "2") (pinfunction "2_2") (pintype "passive"))
      (node (ref "C59") (pin "2") (pinfunction "2_2") (pintype "passive"))
      (node (ref "C6") (pin "-") (pinfunction "-_-") (pintype "passive"))
      (node (ref "C63") (pin "1") (pinfunction "1_1") (pintype "passive"))
      (node (ref "C64") (pin "2") (pinfunction "2_2") (pintype "passive"))
      (node (ref "C65") (pin "2") (pinfunction "2_2") (pintype "passive"))
      (node (ref "C66") (pin "2") (pinfunction "2_2") (pintype "passive"))
      (node (ref "C68") (pin "2") (pinfunction "2_2") (pintype "passive"))
      (node (ref "C7") (pin "2") (pinfunction "2_2") (pintype "passive"))
      (node (ref "C70") (pin "2") (pinfunction "2_2") (pintype "passive"))
      (node (ref "C71") (pin "2") (pinfunction "2_2") (pintype "passive"))
      (node (ref "C72") (pin "1") (pinfunction "1_1") (pintype "passive"))
      (node (ref "C73") (pin "-") (pinfunction "-_-") (pintype "passive"))
      (node (ref "C74") (pin "-") (pinfunction "-_-") (pintype "passive"))
      (node (ref "C75") (pin "2") (pinfunction "2_2") (pintype "passive"))
      (node (ref "C76") (pin "2") (pinfunction "2_2") (pintype "passive"))
      (node (ref "C77") (pin "2") (pinfunction "2_2") (pintype "passive"))
      (node (ref "C78") (pin "2") (pinfunction "2_2") (pintype "passive"))
      (node (ref "C8") (pin "1") (pinfunction "1_1") (pintype "passive"))
      (node (ref "C80") (pin "1") (pinfunction "1_1") (pintype "passive"))
      (node (ref "C81") (pin "2") (pinfunction "2_2") (pintype "passive"))
      (node (ref "C82") (pin "2") (pinfunction "2_2") (pintype "passive"))
      (node (ref "C83") (pin "2") (pinfunction "2_2") (pintype "passive"))
      (node (ref "C87") (pin "1") (pinfunction "1_1") (pintype "passive"))
      (node (ref "C88") (pin "2") (pinfunction "2_2") (pintype "passive"))
      (node (ref "C89") (pin "2") (pinfunction "2_2") (pintype "passive"))
      (node (ref "C9") (pin "2") (pinfunction "2_2") (pintype "passive"))
      (node (ref "C90") (pin "2") (pinfunction "2_2") (pintype "passive"))
      (node (ref "D1") (pin "1") (pinfunction "A_1") (pintype "passive"))
      (node (ref "D1") (pin "3") (pinfunction "A_3") (pintype "passive"))
      (node (ref "ESP") (pin "1") (pinfunction "GND_1") (pintype "power_in"))
      (node (ref "ESP") (pin "15") (pinfunction "GND_15") (pintype "power_in"))
      (node (ref "ESP") (pin "38") (pinfunction "GND_38") (pintype "power_in"))
      (node (ref "ESP") (pin "GND") (pinfunction "GND_GND") (pintype "power_in"))
      (node (ref "GND") (pin "1") (pinfunction "P_1") (pintype "passive"))
      (node (ref "IC1") (pin "1") (pinfunction "GND_1") (pintype "power_in"))
      (node (ref "J1") (pin "4") (pinfunction "GND_4") (pintype "bidirectional"))
      (node (ref "J1") (pin "S1") (pinfunction "SHIELD_S1") (pintype "bidirectional"))
      (node (ref "J1") (pin "S2") (pinfunction "SHIELD_S2") (pintype "bidirectional"))
      (node (ref "J1") (pin "S3") (pinfunction "SHIELD_S3") (pintype "bidirectional"))
      (node (ref "J1") (pin "S4") (pinfunction "SHIELD_S4") (pintype "bidirectional"))
      (node (ref "J2") (pin "4") (pinfunction "GND_4") (pintype "bidirectional"))
      (node (ref "J2") (pin "S1") (pinfunction "SHIELD_S1") (pintype "bidirectional"))
      (node (ref "J2") (pin "S2") (pinfunction "SHIELD_S2") (pintype "bidirectional"))
      (node (ref "J2") (pin "S3") (pinfunction "SHIELD_S3") (pintype "bidirectional"))
      (node (ref "J2") (pin "S4") (pinfunction "SHIELD_S4") (pintype "bidirectional"))
      (node (ref "J3") (pin "3") (pinfunction "3_3") (pintype "passive"))
      (node (ref "J4") (pin "3") (pinfunction "3_3") (pintype "passive"))
      (node (ref "J5") (pin "1") (pinfunction "1_1") (pintype "passive"))
      (node (ref "JP3") (pin "1") (pinfunction "1_1") (pintype "passive"))
      (node (ref "JP7") (pin "1") (pinfunction "1_1") (pintype "passive"))
      (node (ref "PAD1") (pin "1") (pinfunction "P_1") (pintype "passive"))
      (node (ref "PAD11") (pin "1") (pinfunction "P_1") (pintype "passive"))
      (node (ref "PAD12") (pin "1") (pinfunction "P_1") (pintype "passive"))
      (node (ref "PAD3") (pin "1") (pinfunction "P_1") (pintype "passive"))
      (node (ref "PAD8") (pin "1") (pinfunction "P_1") (pintype "passive"))
      (node (ref "PAD9") (pin "1") (pinfunction "P_1") (pintype "passive"))
      (node (ref "R1") (pin "1") (pinfunction "1_1") (pintype "passive"))
      (node (ref "R10") (pin "A") (pinfunction "A_A") (pintype "passive"))
      (node (ref "R11") (pin "A") (pinfunction "A_A") (pintype "passive"))
      (node (ref "R12") (pin "A") (pinfunction "A_A") (pintype "passive"))
      (node (ref "R18") (pin "2") (pinfunction "2_2") (pintype "passive"))
      (node (ref "R26") (pin "1") (pinfunction "1_1") (pintype "passive"))
      (node (ref "R27") (pin "1") (pinfunction "1_1") (pintype "passive"))
      (node (ref "R30") (pin "1") (pinfunction "1_1") (pintype "passive"))
      (node (ref "R33") (pin "1") (pinfunction "1_1") (pintype "passive"))
      (node (ref "R4") (pin "1") (pinfunction "1_1") (pintype "passive"))
      (node (ref "R40") (pin "1") (pinfunction "1_1") (pintype "passive"))
      (node (ref "R41") (pin "1") (pinfunction "1_1") (pintype "passive"))
      (node (ref "R44") (pin "1") (pinfunction "1_1") (pintype "passive"))
      (node (ref "R47") (pin "1") (pinfunction "1_1") (pintype "passive"))
      (node (ref "R6") (pin "1") (pinfunction "1_1") (pintype "passive"))
      (node (ref "R9") (pin "A") (pinfunction "A_A") (pintype "passive"))
      (node (ref "REG1") (pin "7") (pinfunction "GND_7") (pintype "bidirectional"))
      (node (ref "REG1") (pin "EXP") (pinfunction "PWRPD_EXP") (pintype "bidirectional"))
      (node (ref "REG2") (pin "10") (pinfunction "MODE_10") (pintype "input"))
      (node (ref "REG2") (pin "11") (pinfunction "VSEL_11") (pintype "input"))
      (node (ref "REG2") (pin "3") (pinfunction "GND_3") (pintype "power_in"))
      (node (ref "REG2") (pin "4") (pinfunction "FB2_4") (pintype "open_collector"))
      (node (ref "S1") (pin "A2") (pinfunction "1_A2") (pintype "passive"))
      (node (ref "S2") (pin "B2") (pinfunction "2_B2") (pintype "passive"))
      (node (ref "SJ1") (pin "1") (pinfunction "1_1") (pintype "passive"))
      (node (ref "U$1") (pin "-") (pinfunction "GND_-") (pintype "bidirectional"))
      (node (ref "U1") (pin "1") (pinfunction "AGND_2_1") (pintype "power_in"))
      (node (ref "U1") (pin "12") (pinfunction "DGND_2_12") (pintype "power_in"))
      (node (ref "U1") (pin "20") (pinfunction "ADDR1/CDATA/WB_20") (pintype "input"))
      (node (ref "U1") (pin "25") (pinfunction "DGND_25") (pintype "power_in"))
      (node (ref "U1") (pin "30") (pinfunction "RSVD_30") (pintype "passive"))
      (node (ref "U1") (pin "33") (pinfunction "PGND_33") (pintype "power_in"))
      (node (ref "U1") (pin "37") (pinfunction "AGND_3_37") (pintype "power_in"))
      (node (ref "U1") (pin "38") (pinfunction "PLL_MODE0_38") (pintype "input"))
      (node (ref "U1") (pin "42") (pinfunction "AGND_42") (pintype "power_in"))
      (node (ref "U1") (pin "7") (pinfunction "ADDR0_7") (pintype "input"))
      (node (ref "U2") (pin "1") (pinfunction "SUB_GND_1") (pintype "passive"))
      (node (ref "U2") (pin "14") (pinfunction "PGNDA_2_14") (pintype "passive"))
      (node (ref "U2") (pin "15") (pinfunction "PGNDA_15") (pintype "passive"))
      (node (ref "U2") (pin "23") (pinfunction "INNA_23") (pintype "input"))
      (node (ref "U2") (pin "27") (pinfunction "SGND_27") (pintype "passive"))
      (node (ref "U2") (pin "31") (pinfunction "MODE_31") (pintype "passive"))
      (node (ref "U2") (pin "33") (pinfunction "INNB_33") (pintype "input"))
      (node (ref "U2") (pin "4") (pinfunction "PGNDB_2_4") (pintype "passive"))
      (node (ref "U2") (pin "5") (pinfunction "PGNDB_5") (pintype "passive"))
      (node (ref "U2") (pin "EPAD") (pinfunction "EPAD_EPAD") (pintype "passive"))
      (node (ref "U3") (pin "1") (pinfunction "SUB_GND_1") (pintype "passive"))
      (node (ref "U3") (pin "14") (pinfunction "PGNDA_2_14") (pintype "passive"))
      (node (ref "U3") (pin "15") (pinfunction "PGNDA_15") (pintype "passive"))
      (node (ref "U3") (pin "23") (pinfunction "INNA_23") (pintype "input"))
      (node (ref "U3") (pin "27") (pinfunction "SGND_27") (pintype "passive"))
      (node (ref "U3") (pin "31") (pinfunction "MODE_31") (pintype "passive"))
      (node (ref "U3") (pin "33") (pinfunction "INNB_33") (pintype "input"))
      (node (ref "U3") (pin "4") (pinfunction "PGNDB_2_4") (pintype "passive"))
      (node (ref "U3") (pin "5") (pinfunction "PGNDB_5") (pintype "passive"))
      (node (ref "U3") (pin "EPAD") (pinfunction "EPAD_EPAD") (pintype "passive"))
      (node (ref "X1") (pin "2") (pinfunction "KL_2") (pintype "passive"))
    )
    (net (code "82") (name "I2C_SCL") (class "Default")
      (node (ref "ESP") (pin "36") (pinfunction "IO22_36") (pintype "bidirectional"))
      (node (ref "J4") (pin "1") (pinfunction "1_1") (pintype "passive"))
      (node (ref "R13") (pin "2") (pinfunction "2_2") (pintype "passive"))
      (node (ref "U1") (pin "23") (pinfunction "SCL/CCLK_23") (pintype "bidirectional"))
    )
    (net (code "83") (name "I2C_SDA") (class "Default")
      (node (ref "ESP") (pin "33") (pinfunction "IO21_33") (pintype "bidirectional"))
      (node (ref "J4") (pin "2") (pinfunction "2_2") (pintype "passive"))
      (node (ref "R14") (pin "2") (pinfunction "2_2") (pintype "passive"))
      (node (ref "U1") (pin "22") (pinfunction "SDA/COUT_22") (pintype "bidirectional"))
    )
    (net (code "84") (name "LINEIN_SW_L") (class "Default")
      (node (ref "J5") (pin "2") (pinfunction "2_2") (pintype "passive"))
      (node (ref "R19") (pin "2") (pinfunction "2_2") (pintype "passive"))
    )
    (net (code "85") (name "LINEIN_SW_R") (class "Default")
      (node (ref "J5") (pin "3") (pinfunction "3_3") (pintype "passive"))
      (node (ref "R17") (pin "2") (pinfunction "2_2") (pintype "passive"))
    )
    (net (code "86") (name "Net-(C3-Pad1)") (class "Default")
      (node (ref "C3") (pin "1") (pinfunction "1_1") (pintype "passive"))
      (node (ref "R2") (pin "1") (pinfunction "1_1") (pintype "passive"))
    )
    (net (code "87") (name "Net-(C25-Pad1)") (class "Default")
      (node (ref "C25") (pin "1") (pinfunction "1_1") (pintype "passive"))
      (node (ref "Q2") (pin "2") (pinfunction "2_2") (pintype "passive"))
      (node (ref "R20") (pin "2") (pinfunction "2_2") (pintype "passive"))
    )
    (net (code "88") (name "Net-(C34-Pad2)") (class "Default")
      (node (ref "C34") (pin "2") (pinfunction "2_2") (pintype "passive"))
      (node (ref "R21") (pin "2") (pinfunction "2_2") (pintype "passive"))
    )
    (net (code "89") (name "Net-(C35-Pad-)") (class "Default")
      (node (ref "C35") (pin "-") (pinfunction "-_-") (pintype "passive"))
      (node (ref "R22") (pin "2") (pinfunction "2_2") (pintype "passive"))
    )
    (net (code "90") (name "Net-(C37-Pad-)") (class "Default")
      (node (ref "C37") (pin "-") (pinfunction "-_-") (pintype "passive"))
      (node (ref "R23") (pin "2") (pinfunction "2_2") (pintype "passive"))
    )
    (net (code "91") (name "Net-(C39-Pad-)") (class "Default")
      (node (ref "C39") (pin "-") (pinfunction "-_-") (pintype "passive"))
      (node (ref "R24") (pin "2") (pinfunction "2_2") (pintype "passive"))
    )
    (net (code "92") (name "Net-(C41-Pad-)") (class "Default")
      (node (ref "C41") (pin "-") (pinfunction "-_-") (pintype "passive"))
      (node (ref "R25") (pin "2") (pinfunction "2_2") (pintype "passive"))
    )
    (net (code "93") (name "Net-(C55-Pad2)") (class "Default")
      (node (ref "C55") (pin "2") (pinfunction "2_2") (pintype "passive"))
      (node (ref "R34") (pin "1") (pinfunction "1_1") (pintype "passive"))
    )
    (net (code "94") (name "Net-(C58-Pad1)") (class "Default")
      (node (ref "C58") (pin "1") (pinfunction "1_1") (pintype "passive"))
      (node (ref "R36") (pin "2") (pinfunction "2_2") (pintype "passive"))
    )
    (net (code "95") (name "Net-(C59-Pad1)") (class "Default")
      (node (ref "C59") (pin "1") (pinfunction "1_1") (pintype "passive"))
      (node (ref "R35") (pin "2") (pinfunction "2_2") (pintype "passive"))
    )
    (net (code "96") (name "Net-(C61-Pad2)") (class "Default")
      (node (ref "C61") (pin "2") (pinfunction "2_2") (pintype "passive"))
      (node (ref "R37") (pin "1") (pinfunction "1_1") (pintype "passive"))
    )
    (net (code "97") (name "Net-(C65-Pad1)") (class "Default")
      (node (ref "C65") (pin "1") (pinfunction "1_1") (pintype "passive"))
      (node (ref "R38") (pin "2") (pinfunction "2_2") (pintype "passive"))
    )
    (net (code "98") (name "Net-(C66-Pad1)") (class "Default")
      (node (ref "C66") (pin "1") (pinfunction "1_1") (pintype "passive"))
      (node (ref "R39") (pin "2") (pinfunction "2_2") (pintype "passive"))
    )
    (net (code "99") (name "Net-(C79-Pad2)") (class "Default")
      (node (ref "C79") (pin "2") (pinfunction "2_2") (pintype "passive"))
      (node (ref "R48") (pin "1") (pinfunction "1_1") (pintype "passive"))
    )
    (net (code "100") (name "Net-(C82-Pad1)") (class "Default")
      (node (ref "C82") (pin "1") (pinfunction "1_1") (pintype "passive"))
      (node (ref "R50") (pin "2") (pinfunction "2_2") (pintype "passive"))
    )
    (net (code "101") (name "Net-(C83-Pad1)") (class "Default")
      (node (ref "C83") (pin "1") (pinfunction "1_1") (pintype "passive"))
      (node (ref "R49") (pin "2") (pinfunction "2_2") (pintype "passive"))
    )
    (net (code "102") (name "Net-(C85-Pad2)") (class "Default")
      (node (ref "C85") (pin "2") (pinfunction "2_2") (pintype "passive"))
      (node (ref "R51") (pin "1") (pinfunction "1_1") (pintype "passive"))
    )
    (net (code "103") (name "Net-(C89-Pad1)") (class "Default")
      (node (ref "C89") (pin "1") (pinfunction "1_1") (pintype "passive"))
      (node (ref "R52") (pin "2") (pinfunction "2_2") (pintype "passive"))
    )
    (net (code "104") (name "Net-(C90-Pad1)") (class "Default")
      (node (ref "C90") (pin "1") (pinfunction "1_1") (pintype "passive"))
      (node (ref "R53") (pin "2") (pinfunction "2_2") (pintype "passive"))
    )
    (net (code "105") (name "Net-(JP1-Pad1)") (class "Default")
      (node (ref "JP1") (pin "1") (pinfunction "1_1") (pintype "passive"))
      (node (ref "R31") (pin "1") (pinfunction "1_1") (pintype "passive"))
      (node (ref "R32") (pin "2") (pinfunction "2_2") (pintype "passive"))
    )
    (net (code "106") (name "Net-(JP2-Pad1)") (class "Default")
      (node (ref "JP2") (pin "1") (pinfunction "1_1") (pintype "passive"))
      (node (ref "R32") (pin "1") (pinfunction "1_1") (pintype "passive"))
      (node (ref "R33") (pin "2") (pinfunction "2_2") (pintype "passive"))
    )
    (net (code "107") (name "Net-(JP5-Pad1)") (class "Default")
      (node (ref "JP5") (pin "1") (pinfunction "1_1") (pintype "passive"))
      (node (ref "R45") (pin "1") (pinfunction "1_1") (pintype "passive"))
      (node (ref "R46") (pin "2") (pinfunction "2_2") (pintype "passive"))
    )
    (net (code "108") (name "Net-(JP6-Pad1)") (class "Default")
      (node (ref "JP6") (pin "1") (pinfunction "1_1") (pintype "passive"))
      (node (ref "R46") (pin "1") (pinfunction "1_1") (pintype "passive"))
      (node (ref "R47") (pin "2") (pinfunction "2_2") (pintype "passive"))
    )
    (net (code "109") (name "Net-(L2-1)") (class "Default")
      (node (ref "L2") (pin "P$1") (pinfunction "1_P$1") (pintype "passive"))
      (node (ref "REG2") (pin "2") (pinfunction "SW_2") (pintype "power_in"))
    )
    (net (code "110") (name "Net-(REG1-BOOT)") (class "Default")
      (node (ref "C5") (pin "1") (pinfunction "1_1") (pintype "passive"))
      (node (ref "REG1") (pin "1") (pinfunction "BOOT_1") (pintype "bidirectional"))
    )
    (net (code "111") (name "Net-(REG1-COMP)") (class "Default")
      (node (ref "C4") (pin "1") (pinfunction "1_1") (pintype "passive"))
      (node (ref "R2") (pin "2") (pinfunction "2_2") (pintype "passive"))
      (node (ref "REG1") (pin "6") (pinfunction "COMP_6") (pintype "bidirectional"))
    )
    (net (code "112") (name "Net-(REG1-FB)") (class "Default")
      (node (ref "R3") (pin "1") (pinfunction "1_1") (pintype "passive"))
      (node (ref "R4") (pin "2") (pinfunction "2_2") (pintype "passive"))
      (node (ref "REG1") (pin "5") (pinfunction "FB_5") (pintype "bidirectional"))
    )
    (net (code "113") (name "Net-(REG1-RT_CLK)") (class "Default")
      (node (ref "R1") (pin "2") (pinfunction "2_2") (pintype "passive"))
      (node (ref "REG1") (pin "4") (pinfunction "RT_CLK_4") (pintype "bidirectional"))
    )
    (net (code "114") (name "Net-(REG2-FB)") (class "Default")
      (node (ref "R6") (pin "2") (pinfunction "2_2") (pintype "passive"))
      (node (ref "R7") (pin "1") (pinfunction "1_1") (pintype "passive"))
      (node (ref "REG2") (pin "5") (pinfunction "FB_5") (pintype "input"))
    )
    (net (code "115") (name "Net-(REG2-PG)") (class "Default")
      (node (ref "R5") (pin "1") (pinfunction "1_1") (pintype "passive"))
      (node (ref "REG2") (pin "7") (pinfunction "PG_7") (pintype "open_collector"))
    )
    (net (code "116") (name "Net-(REG2-SS_TR)") (class "Default")
      (node (ref "C8") (pin "2") (pinfunction "2_2") (pintype "passive"))
      (node (ref "REG2") (pin "9") (pinfunction "SS_TR_9") (pintype "input"))
    )
    (net (code "117") (name "Net-(U1A-ADC0)") (class "Default")
      (node (ref "R17") (pin "1") (pinfunction "1_1") (pintype "passive"))
      (node (ref "U1") (pin "2") (pinfunction "ADC0_2") (pintype "input"))
    )
    (net (code "118") (name "Net-(U1A-ADC1)") (class "Default")
      (node (ref "R19") (pin "1") (pinfunction "1_1") (pintype "passive"))
      (node (ref "U1") (pin "4") (pinfunction "ADC1_4") (pintype "input"))
    )
    (net (code "119") (name "Net-(U1A-ADC_RES)") (class "Default")
      (node (ref "R18") (pin "1") (pinfunction "1_1") (pintype "passive"))
      (node (ref "U1") (pin "3") (pinfunction "ADC_RES_3") (pintype "input"))
    )
    (net (code "120") (name "Net-(U1A-CM)") (class "Default")
      (node (ref "C31") (pin "2") (pinfunction "2_2") (pintype "passive"))
      (node (ref "C32") (pin "2") (pinfunction "2_2") (pintype "passive"))
      (node (ref "U1") (pin "40") (pinfunction "CM_40") (pintype "output"))
    )
    (net (code "121") (name "Net-(U1A-FILTA)") (class "Default")
      (node (ref "C29") (pin "2") (pinfunction "2_2") (pintype "passive"))
      (node (ref "C30") (pin "2") (pinfunction "2_2") (pintype "passive"))
      (node (ref "U1") (pin "47") (pinfunction "FILTA_47") (pintype "output"))
    )
    (net (code "122") (name "Net-(U1A-FILTD)") (class "Default")
      (node (ref "C27") (pin "2") (pinfunction "2_2") (pintype "passive"))
      (node (ref "C28") (pin "2") (pinfunction "2_2") (pintype "passive"))
      (node (ref "U1") (pin "41") (pinfunction "FILTD_41") (pintype "output"))
    )
    (net (code "123") (name "Net-(U1A-PLL_LF)") (class "Default")
      (node (ref "C33") (pin "1") (pinfunction "1_1") (pintype "passive"))
      (node (ref "C34") (pin "1") (pinfunction "1_1") (pintype "passive"))
      (node (ref "U1") (pin "35") (pinfunction "PLL_LF_35") (pintype "output"))
    )
    (net (code "124") (name "Net-(U2A-DIAG)") (class "Default")
      (node (ref "R29") (pin "1") (pinfunction "1_1") (pintype "passive"))
      (node (ref "U2") (pin "28") (pinfunction "DIAG_28") (pintype "passive"))
    )
    (net (code "125") (name "Net-(U2A-SVCC)") (class "Default")
      (node (ref "C43") (pin "2") (pinfunction "2_2") (pintype "passive"))
      (node (ref "U2") (pin "35") (pinfunction "SVCC_35") (pintype "passive"))
    )
    (net (code "126") (name "Net-(U2A-SVR)") (class "Default")
      (node (ref "C44") (pin "1") (pinfunction "1_1") (pintype "passive"))
      (node (ref "U2") (pin "29") (pinfunction "SVR_29") (pintype "passive"))
    )
    (net (code "127") (name "Net-(U3A-DIAG)") (class "Default")
      (node (ref "R43") (pin "1") (pinfunction "1_1") (pintype "passive"))
      (node (ref "U3") (pin "28") (pinfunction "DIAG_28") (pintype "passive"))
    )
    (net (code "128") (name "Net-(U3A-SVCC)") (class "Default")
      (node (ref "C67") (pin "2") (pinfunction "2_2") (pintype "passive"))
      (node (ref "U3") (pin "35") (pinfunction "SVCC_35") (pintype "passive"))
    )
    (net (code "129") (name "Net-(U3A-SVR)") (class "Default")
      (node (ref "C68") (pin "1") (pinfunction "1_1") (pintype "passive"))
      (node (ref "U3") (pin "29") (pinfunction "SVR_29") (pintype "passive"))
    )
    (net (code "130") (name "OUTA_N") (class "Default")
      (node (ref "C62") (pin "2") (pinfunction "2_2") (pintype "passive"))
      (node (ref "C64") (pin "1") (pinfunction "1_1") (pintype "passive"))
      (node (ref "L6") (pin "P$2") (pinfunction "2_P$2") (pintype "passive"))
      (node (ref "OUT_A_-") (pin "1") (pinfunction "P_1") (pintype "passive"))
      (node (ref "R39") (pin "1") (pinfunction "1_1") (pintype "passive"))
    )
    (net (code "131") (name "OUTA_P") (class "Default")
      (node (ref "C62") (pin "1") (pinfunction "1_1") (pintype "passive"))
      (node (ref "C63") (pin "2") (pinfunction "2_2") (pintype "passive"))
      (node (ref "L5") (pin "P$2") (pinfunction "2_P$2") (pintype "passive"))
      (node (ref "OUT_A_+") (pin "1") (pinfunction "P_1") (pintype "passive"))
      (node (ref "R38") (pin "1") (pinfunction "1_1") (pintype "passive"))
    )
    (net (code "132") (name "OUTB_N") (class "Default")
      (node (ref "C57") (pin "1") (pinfunction "1_1") (pintype "passive"))
      (node (ref "C60") (pin "2") (pinfunction "2_2") (pintype "passive"))
      (node (ref "L4") (pin "P$2") (pinfunction "2_P$2") (pintype "passive"))
      (node (ref "OUT_B_-") (pin "1") (pinfunction "P_1") (pintype "passive"))
      (node (ref "R35") (pin "1") (pinfunction "1_1") (pintype "passive"))
    )
    (net (code "133") (name "OUTB_P") (class "Default")
      (node (ref "C56") (pin "2") (pinfunction "2_2") (pintype "passive"))
      (node (ref "C60") (pin "1") (pinfunction "1_1") (pintype "passive"))
      (node (ref "L3") (pin "P$2") (pinfunction "2_P$2") (pintype "passive"))
      (node (ref "OUT_B_+") (pin "1") (pinfunction "P_1") (pintype "passive"))
      (node (ref "R36") (pin "1") (pinfunction "1_1") (pintype "passive"))
    )
    (net (code "134") (name "OUTC_N") (class "Default")
      (node (ref "C86") (pin "2") (pinfunction "2_2") (pintype "passive"))
      (node (ref "C88") (pin "1") (pinfunction "1_1") (pintype "passive"))
      (node (ref "L10") (pin "P$2") (pinfunction "2_P$2") (pintype "passive"))
      (node (ref "OUT_C_-") (pin "1") (pinfunction "P_1") (pintype "passive"))
      (node (ref "R53") (pin "1") (pinfunction "1_1") (pintype "passive"))
    )
    (net (code "135") (name "OUTC_P") (class "Default")
      (node (ref "C86") (pin "1") (pinfunction "1_1") (pintype "passive"))
      (node (ref "C87") (pin "2") (pinfunction "2_2") (pintype "passive"))
      (node (ref "L9") (pin "P$2") (pinfunction "2_P$2") (pintype "passive"))
      (node (ref "OUT_C_+") (pin "1") (pinfunction "P_1") (pintype "passive"))
      (node (ref "R52") (pin "1") (pinfunction "1_1") (pintype "passive"))
    )
    (net (code "136") (name "OUTD_N") (class "Default")
      (node (ref "C81") (pin "1") (pinfunction "1_1") (pintype "passive"))
      (node (ref "C84") (pin "2") (pinfunction "2_2") (pintype "passive"))
      (node (ref "L8") (pin "P$2") (pinfunction "2_P$2") (pintype "passive"))
      (node (ref "OUT_D_-") (pin "1") (pinfunction "P_1") (pintype "passive"))
      (node (ref "R49") (pin "1") (pinfunction "1_1") (pintype "passive"))
    )
    (net (code "137") (name "OUTD_P") (class "Default")
      (node (ref "C80") (pin "2") (pinfunction "2_2") (pintype "passive"))
      (node (ref "C84") (pin "1") (pinfunction "1_1") (pintype "passive"))
      (node (ref "L7") (pin "P$2") (pinfunction "2_P$2") (pintype "passive"))
      (node (ref "OUT_D_+") (pin "1") (pinfunction "P_1") (pintype "passive"))
      (node (ref "R50") (pin "1") (pinfunction "1_1") (pintype "passive"))
    )
    (net (code "138") (name "P12V_EN") (class "Default")
      (node (ref "REG1") (pin "3") (pinfunction "EN_3") (pintype "bidirectional"))
    )
    (net (code "139") (name "POT0") (class "Default")
      (node (ref "R9") (pin "S") (pinfunction "S_S") (pintype "passive"))
      (node (ref "U1") (pin "26") (pinfunction "MP9_26") (pintype "bidirectional"))
    )
    (net (code "140") (name "POT1") (class "Default")
      (node (ref "R10") (pin "S") (pinfunction "S_S") (pintype "passive"))
      (node (ref "U1") (pin "27") (pinfunction "MP8_27") (pintype "bidirectional"))
    )
    (net (code "141") (name "POT2") (class "Default")
      (node (ref "R11") (pin "S") (pinfunction "S_S") (pintype "passive"))
      (node (ref "U1") (pin "28") (pinfunction "MP3_28") (pintype "bidirectional"))
    )
    (net (code "142") (name "POT3") (class "Default")
      (node (ref "R12") (pin "S") (pinfunction "S_S") (pintype "passive"))
      (node (ref "U1") (pin "29") (pinfunction "MP2_29") (pintype "bidirectional"))
    )
    (net (code "143") (name "R12V_SW") (class "Default")
      (node (ref "C5") (pin "2") (pinfunction "2_2") (pintype "passive"))
      (node (ref "D1") (pin "2") (pinfunction "C_2") (pintype "passive"))
      (node (ref "L1") (pin "P$1") (pinfunction "1_P$1") (pintype "passive"))
      (node (ref "REG1") (pin "8") (pinfunction "SW_8") (pintype "bidirectional"))
    )
    (net (code "144") (name "V+") (class "Default")
      (node (ref "C1") (pin "+") (pinfunction "+_+") (pintype "passive"))
      (node (ref "C2") (pin "+") (pinfunction "+_+") (pintype "passive"))
      (node (ref "C49") (pin "+") (pinfunction "+_+") (pintype "passive"))
      (node (ref "C50") (pin "+") (pinfunction "+_+") (pintype "passive"))
      (node (ref "C51") (pin "1") (pinfunction "1_1") (pintype "passive"))
      (node (ref "C52") (pin "1") (pinfunction "1_1") (pintype "passive"))
      (node (ref "C53") (pin "1") (pinfunction "1_1") (pintype "passive"))
      (node (ref "C54") (pin "1") (pinfunction "1_1") (pintype "passive"))
      (node (ref "C7") (pin "1") (pinfunction "1_1") (pintype "passive"))
      (node (ref "C73") (pin "+") (pinfunction "+_+") (pintype "passive"))
      (node (ref "C74") (pin "+") (pinfunction "+_+") (pintype "passive"))
      (node (ref "C75") (pin "1") (pinfunction "1_1") (pintype "passive"))
      (node (ref "C76") (pin "1") (pinfunction "1_1") (pintype "passive"))
      (node (ref "C77") (pin "1") (pinfunction "1_1") (pintype "passive"))
      (node (ref "C78") (pin "1") (pinfunction "1_1") (pintype "passive"))
      (node (ref "REG1") (pin "2") (pinfunction "VIN_2") (pintype "bidirectional"))
      (node (ref "U$1") (pin "+") (pinfunction "VCC_+") (pintype "bidirectional"))
      (node (ref "U2") (pin "12") (pinfunction "PVCCA_2_12") (pintype "passive"))
      (node (ref "U2") (pin "13") (pinfunction "PVCCA_13") (pintype "passive"))
      (node (ref "U2") (pin "6") (pinfunction "PVCCB_2_6") (pintype "passive"))
      (node (ref "U2") (pin "7") (pinfunction "PVCCB_7") (pintype "passive"))
      (node (ref "U3") (pin "12") (pinfunction "PVCCA_2_12") (pintype "passive"))
      (node (ref "U3") (pin "13") (pinfunction "PVCCA_13") (pintype "passive"))
      (node (ref "U3") (pin "6") (pinfunction "PVCCB_2_6") (pintype "passive"))
      (node (ref "U3") (pin "7") (pinfunction "PVCCB_7") (pintype "passive"))
      (node (ref "VIN") (pin "1") (pinfunction "P_1") (pintype "passive"))
    )
    (net (code "145") (name "unconnected-(J1-D+-Pad3)") (class "Default")
      (node (ref "J1") (pin "3") (pinfunction "D+_3") (pintype "bidirectional"))
    )
    (net (code "146") (name "unconnected-(J1-D--Pad2)") (class "Default")
      (node (ref "J1") (pin "2") (pinfunction "D-_2") (pintype "bidirectional"))
    )
    (net (code "147") (name "unconnected-(J2-D+-Pad3)") (class "Default")
      (node (ref "J2") (pin "3") (pinfunction "D+_3") (pintype "bidirectional"))
    )
    (net (code "148") (name "unconnected-(J2-D--Pad2)") (class "Default")
      (node (ref "J2") (pin "2") (pinfunction "D-_2") (pintype "bidirectional"))
    )
    (net (code "149") (name "unconnected-(U1A-CLATCH{slash}WP-Pad21)") (class "Default")
      (node (ref "U1") (pin "21") (pinfunction "CLATCH/WP_21") (pintype "bidirectional"))
    )
  )
)
